# orbiphone.net
KiCad netlist of a schematic drawn in EAGLE
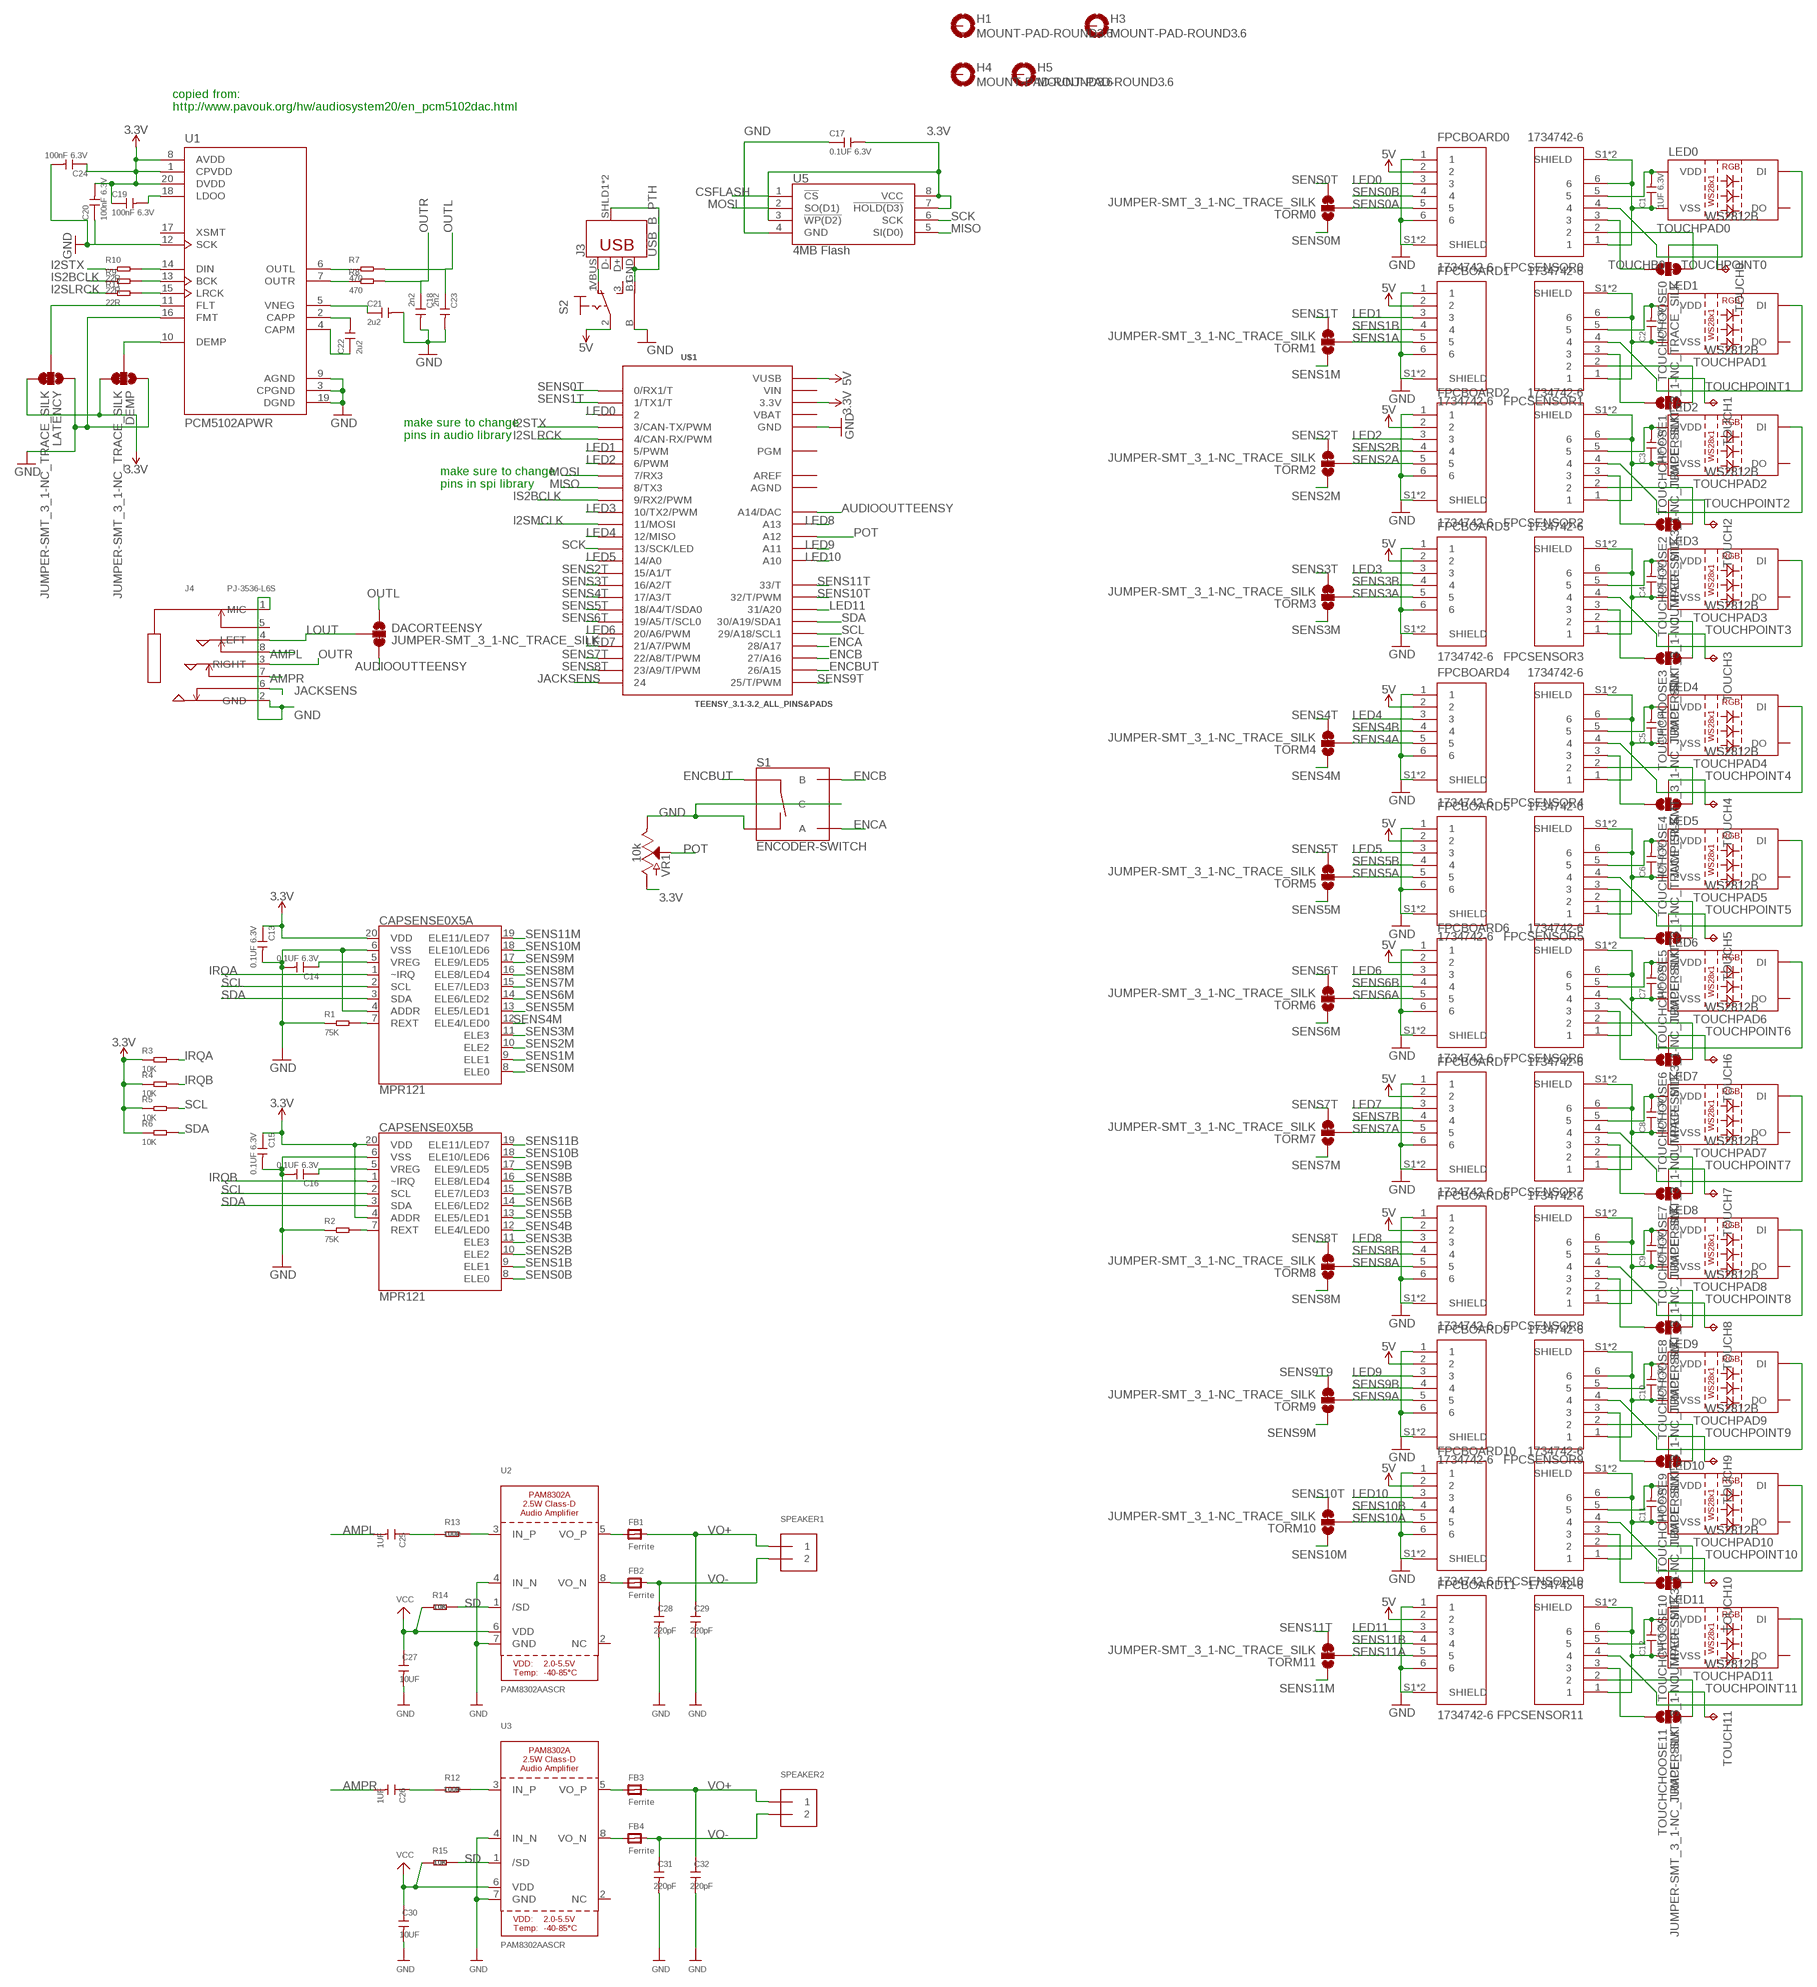
[diagram p0: schematic, sheet 1]

(export (version "E")
  (design (tool "Eeschema 10.0.6"))
  (components
    (comp (ref "C1")
      (value "1UF 6.3V")
      (footprint "eagle-import:C0402")
      (fields (field (name "MPN") "CC0402KRX5R5BB105"))
      (libsource (lib "eagle-import") (part "CERAMIC-1UF-6.3V-10%-X5R(0402)"))
    )
    (comp (ref "C2")
      (value "1UF 6.3V")
      (footprint "eagle-import:C0402")
      (fields (field (name "MPN") "CC0402KRX5R5BB105"))
      (libsource (lib "eagle-import") (part "CERAMIC-1UF-6.3V-10%-X5R(0402)"))
    )
    (comp (ref "C3")
      (value "1UF 6.3V")
      (footprint "eagle-import:C0402")
      (fields (field (name "MPN") "CC0402KRX5R5BB105"))
      (libsource (lib "eagle-import") (part "CERAMIC-1UF-6.3V-10%-X5R(0402)"))
    )
    (comp (ref "C4")
      (value "1UF 6.3V")
      (footprint "eagle-import:C0402")
      (fields (field (name "MPN") "CC0402KRX5R5BB105"))
      (libsource (lib "eagle-import") (part "CERAMIC-1UF-6.3V-10%-X5R(0402)"))
    )
    (comp (ref "C5")
      (value "1UF 6.3V")
      (footprint "eagle-import:C0402")
      (fields (field (name "MPN") "CC0402KRX5R5BB105"))
      (libsource (lib "eagle-import") (part "CERAMIC-1UF-6.3V-10%-X5R(0402)"))
    )
    (comp (ref "C6")
      (value "1UF 6.3V")
      (footprint "eagle-import:C0402")
      (fields (field (name "MPN") "CC0402KRX5R5BB105"))
      (libsource (lib "eagle-import") (part "CERAMIC-1UF-6.3V-10%-X5R(0402)"))
    )
    (comp (ref "C7")
      (value "1UF 6.3V")
      (footprint "eagle-import:C0402")
      (fields (field (name "MPN") "CC0402KRX5R5BB105"))
      (libsource (lib "eagle-import") (part "CERAMIC-1UF-6.3V-10%-X5R(0402)"))
    )
    (comp (ref "C8")
      (value "1UF 6.3V")
      (footprint "eagle-import:C0402")
      (fields (field (name "MPN") "CC0402KRX5R5BB105"))
      (libsource (lib "eagle-import") (part "CERAMIC-1UF-6.3V-10%-X5R(0402)"))
    )
    (comp (ref "C9")
      (value "1UF 6.3V")
      (footprint "eagle-import:C0402")
      (fields (field (name "MPN") "CC0402KRX5R5BB105"))
      (libsource (lib "eagle-import") (part "CERAMIC-1UF-6.3V-10%-X5R(0402)"))
    )
    (comp (ref "C10")
      (value "1UF 6.3V")
      (footprint "eagle-import:C0402")
      (fields (field (name "MPN") "CC0402KRX5R5BB105"))
      (libsource (lib "eagle-import") (part "CERAMIC-1UF-6.3V-10%-X5R(0402)"))
    )
    (comp (ref "C11")
      (value "1UF 6.3V")
      (footprint "eagle-import:C0402")
      (fields (field (name "MPN") "CC0402KRX5R5BB105"))
      (libsource (lib "eagle-import") (part "CERAMIC-1UF-6.3V-10%-X5R(0402)"))
    )
    (comp (ref "C12")
      (value "1UF 6.3V")
      (footprint "eagle-import:C0402")
      (fields (field (name "MPN") "CC0402KRX5R5BB105"))
      (libsource (lib "eagle-import") (part "CERAMIC-1UF-6.3V-10%-X5R(0402)"))
    )
    (comp (ref "C13")
      (value "0.1UF 6.3V")
      (footprint "eagle-import:C0402")
      (fields (field (name "MPN") "CC0402KRX5R5BB105"))
      (libsource (lib "eagle-import") (part "CERAMIC-1UF-6.3V-10%-X5R(0402)"))
    )
    (comp (ref "C14")
      (value "0.1UF 6.3V")
      (footprint "eagle-import:C0402")
      (fields (field (name "MPN") "CC0402KRX5R5BB105"))
      (libsource (lib "eagle-import") (part "CERAMIC-1UF-6.3V-10%-X5R(0402)"))
    )
    (comp (ref "C15")
      (value "0.1UF 6.3V")
      (footprint "eagle-import:C0402")
      (fields (field (name "MPN") "CC0402KRX5R5BB105"))
      (libsource (lib "eagle-import") (part "CERAMIC-1UF-6.3V-10%-X5R(0402)"))
    )
    (comp (ref "C16")
      (value "0.1UF 6.3V")
      (footprint "eagle-import:C0402")
      (fields (field (name "MPN") "CC0402KRX5R5BB105"))
      (libsource (lib "eagle-import") (part "CERAMIC-1UF-6.3V-10%-X5R(0402)"))
    )
    (comp (ref "C17")
      (value "0.1UF 6.3V")
      (footprint "eagle-import:C0402")
      (fields (field (name "MPN") "CC0402KRX5R5BB105"))
      (libsource (lib "eagle-import") (part "CERAMIC-1UF-6.3V-10%-X5R(0402)"))
    )
    (comp (ref "C18")
      (value "2n2")
      (footprint "eagle-import:C0402")
      (fields (field (name "MPN") "CC0402KRX5R5BB105"))
      (libsource (lib "eagle-import") (part "CERAMIC-1UF-6.3V-10%-X5R(0402)"))
    )
    (comp (ref "C19")
      (value "100nF 6.3V")
      (footprint "eagle-import:C0402")
      (fields (field (name "MPN") "CC0402KRX5R5BB105"))
      (libsource (lib "eagle-import") (part "CERAMIC-1UF-6.3V-10%-X5R(0402)"))
    )
    (comp (ref "C20")
      (value "100nF 6.3V")
      (footprint "eagle-import:C0402")
      (fields (field (name "MPN") "CC0402KRX5R5BB105"))
      (libsource (lib "eagle-import") (part "CERAMIC-1UF-6.3V-10%-X5R(0402)"))
    )
    (comp (ref "C21")
      (value "2u2")
      (footprint "eagle-import:C0402")
      (fields (field (name "MPN") "CC0402KRX5R5BB105"))
      (libsource (lib "eagle-import") (part "CERAMIC-1UF-6.3V-10%-X5R(0402)"))
    )
    (comp (ref "C22")
      (value "2u2")
      (footprint "eagle-import:C0402")
      (fields (field (name "MPN") "CC0402KRX5R5BB105"))
      (libsource (lib "eagle-import") (part "CERAMIC-1UF-6.3V-10%-X5R(0402)"))
    )
    (comp (ref "C23")
      (value "2n2")
      (footprint "eagle-import:C0402")
      (fields (field (name "MPN") "CC0402KRX5R5BB105"))
      (libsource (lib "eagle-import") (part "CERAMIC-1UF-6.3V-10%-X5R(0402)"))
    )
    (comp (ref "C24")
      (value "100nF 6.3V")
      (footprint "eagle-import:C0402")
      (fields (field (name "MPN") "CC0402KRX5R5BB105"))
      (libsource (lib "eagle-import") (part "CERAMIC-1UF-6.3V-10%-X5R(0402)"))
    )
    (comp (ref "C25")
      (value "1UF")
      (footprint "eagle-import:C0402")
      (fields (field (name "MPN") "CC0402KRX5R5BB105"))
      (libsource (lib "eagle-import") (part "CERAMIC-1UF-6.3V-10%-X5R(0402)"))
    )
    (comp (ref "C26")
      (value "1UF")
      (footprint "eagle-import:C0402")
      (fields (field (name "MPN") "CC0402KRX5R5BB105"))
      (libsource (lib "eagle-import") (part "CERAMIC-1UF-6.3V-10%-X5R(0402)"))
    )
    (comp (ref "C27")
      (value "10UF")
      (footprint "eagle-import:C0402")
      (fields (field (name "MPN") "CC0402KRX5R5BB105"))
      (libsource (lib "eagle-import") (part "CERAMIC-1UF-6.3V-10%-X5R(0402)"))
    )
    (comp (ref "C28")
      (value "220pF")
      (footprint "eagle-import:C0402")
      (fields (field (name "MPN") "CC0402KRX5R5BB105"))
      (libsource (lib "eagle-import") (part "CERAMIC-1UF-6.3V-10%-X5R(0402)"))
    )
    (comp (ref "C29")
      (value "220pF")
      (footprint "eagle-import:C0402")
      (fields (field (name "MPN") "CC0402KRX5R5BB105"))
      (libsource (lib "eagle-import") (part "CERAMIC-1UF-6.3V-10%-X5R(0402)"))
    )
    (comp (ref "C30")
      (value "10UF")
      (footprint "eagle-import:C0402")
      (fields (field (name "MPN") "CC0402KRX5R5BB105"))
      (libsource (lib "eagle-import") (part "CERAMIC-1UF-6.3V-10%-X5R(0402)"))
    )
    (comp (ref "C31")
      (value "220pF")
      (footprint "eagle-import:C0402")
      (fields (field (name "MPN") "CC0402KRX5R5BB105"))
      (libsource (lib "eagle-import") (part "CERAMIC-1UF-6.3V-10%-X5R(0402)"))
    )
    (comp (ref "C32")
      (value "220pF")
      (footprint "eagle-import:C0402")
      (fields (field (name "MPN") "CC0402KRX5R5BB105"))
      (libsource (lib "eagle-import") (part "CERAMIC-1UF-6.3V-10%-X5R(0402)"))
    )
    (comp (ref "CAPSENSE0X5A")
      (value "MPR121")
      (footprint "eagle-import:QFN-20")
      (libsource (lib "eagle-import") (part "MPR121"))
    )
    (comp (ref "CAPSENSE0X5B")
      (value "MPR121")
      (footprint "eagle-import:QFN-20")
      (libsource (lib "eagle-import") (part "MPR121"))
    )
    (comp (ref "DACORTEENSY")
      (value "JUMPER-SMT_3_1-NC_TRACE_SILK")
      (footprint "eagle-import:SMT-JUMPER_3_1-NC_TRACE_SILK")
      (libsource (lib "eagle-import") (part "JUMPER-SMT_3_1-NC_TRACE_SILK"))
    )
    (comp (ref "DEMP")
      (value "JUMPER-SMT_3_1-NC_TRACE_SILK")
      (footprint "eagle-import:SMT-JUMPER_3_1-NC_TRACE_SILK")
      (libsource (lib "eagle-import") (part "JUMPER-SMT_3_1-NC_TRACE_SILK"))
    )
    (comp (ref "FB1")
      (value "Ferrite")
      (footprint "eagle-import:_0805")
      (libsource (lib "eagle-import") (part "FERRITE_0805"))
    )
    (comp (ref "FB2")
      (value "Ferrite")
      (footprint "eagle-import:_0805")
      (libsource (lib "eagle-import") (part "FERRITE_0805"))
    )
    (comp (ref "FB3")
      (value "Ferrite")
      (footprint "eagle-import:_0805")
      (libsource (lib "eagle-import") (part "FERRITE_0805"))
    )
    (comp (ref "FB4")
      (value "Ferrite")
      (footprint "eagle-import:_0805")
      (libsource (lib "eagle-import") (part "FERRITE_0805"))
    )
    (comp (ref "FPCBOARD0")
      (value "1734742-6")
      (footprint "eagle-import:TE_1734742-6")
      (fields (field (name "MF") "TE Connectivity"))
      (libsource (lib "eagle-import") (part "1734742-6"))
    )
    (comp (ref "FPCBOARD1")
      (value "1734742-6")
      (footprint "eagle-import:TE_1734742-6")
      (fields (field (name "MF") "TE Connectivity"))
      (libsource (lib "eagle-import") (part "1734742-6"))
    )
    (comp (ref "FPCBOARD2")
      (value "1734742-6")
      (footprint "eagle-import:TE_1734742-6")
      (fields (field (name "MF") "TE Connectivity"))
      (libsource (lib "eagle-import") (part "1734742-6"))
    )
    (comp (ref "FPCBOARD3")
      (value "1734742-6")
      (footprint "eagle-import:TE_1734742-6")
      (fields (field (name "MF") "TE Connectivity"))
      (libsource (lib "eagle-import") (part "1734742-6"))
    )
    (comp (ref "FPCBOARD4")
      (value "1734742-6")
      (footprint "eagle-import:TE_1734742-6")
      (fields (field (name "MF") "TE Connectivity"))
      (libsource (lib "eagle-import") (part "1734742-6"))
    )
    (comp (ref "FPCBOARD5")
      (value "1734742-6")
      (footprint "eagle-import:TE_1734742-6")
      (fields (field (name "MF") "TE Connectivity"))
      (libsource (lib "eagle-import") (part "1734742-6"))
    )
    (comp (ref "FPCBOARD6")
      (value "1734742-6")
      (footprint "eagle-import:TE_1734742-6")
      (fields (field (name "MF") "TE Connectivity"))
      (libsource (lib "eagle-import") (part "1734742-6"))
    )
    (comp (ref "FPCBOARD7")
      (value "1734742-6")
      (footprint "eagle-import:TE_1734742-6")
      (fields (field (name "MF") "TE Connectivity"))
      (libsource (lib "eagle-import") (part "1734742-6"))
    )
    (comp (ref "FPCBOARD8")
      (value "1734742-6")
      (footprint "eagle-import:TE_1734742-6")
      (fields (field (name "MF") "TE Connectivity"))
      (libsource (lib "eagle-import") (part "1734742-6"))
    )
    (comp (ref "FPCBOARD9")
      (value "1734742-6")
      (footprint "eagle-import:TE_1734742-6")
      (fields (field (name "MF") "TE Connectivity"))
      (libsource (lib "eagle-import") (part "1734742-6"))
    )
    (comp (ref "FPCBOARD10")
      (value "1734742-6")
      (footprint "eagle-import:TE_1734742-6")
      (fields (field (name "MF") "TE Connectivity"))
      (libsource (lib "eagle-import") (part "1734742-6"))
    )
    (comp (ref "FPCBOARD11")
      (value "1734742-6")
      (footprint "eagle-import:TE_1734742-6")
      (fields (field (name "MF") "TE Connectivity"))
      (libsource (lib "eagle-import") (part "1734742-6"))
    )
    (comp (ref "FPCSENSOR0")
      (value "1734742-6")
      (footprint "eagle-import:TE_1734742-6")
      (fields (field (name "MF") "TE Connectivity"))
      (libsource (lib "eagle-import") (part "1734742-6"))
    )
    (comp (ref "FPCSENSOR1")
      (value "1734742-6")
      (footprint "eagle-import:TE_1734742-6")
      (fields (field (name "MF") "TE Connectivity"))
      (libsource (lib "eagle-import") (part "1734742-6"))
    )
    (comp (ref "FPCSENSOR2")
      (value "1734742-6")
      (footprint "eagle-import:TE_1734742-6")
      (fields (field (name "MF") "TE Connectivity"))
      (libsource (lib "eagle-import") (part "1734742-6"))
    )
    (comp (ref "FPCSENSOR3")
      (value "1734742-6")
      (footprint "eagle-import:TE_1734742-6")
      (fields (field (name "MF") "TE Connectivity"))
      (libsource (lib "eagle-import") (part "1734742-6"))
    )
    (comp (ref "FPCSENSOR4")
      (value "1734742-6")
      (footprint "eagle-import:TE_1734742-6")
      (fields (field (name "MF") "TE Connectivity"))
      (libsource (lib "eagle-import") (part "1734742-6"))
    )
    (comp (ref "FPCSENSOR5")
      (value "1734742-6")
      (footprint "eagle-import:TE_1734742-6")
      (fields (field (name "MF") "TE Connectivity"))
      (libsource (lib "eagle-import") (part "1734742-6"))
    )
    (comp (ref "FPCSENSOR6")
      (value "1734742-6")
      (footprint "eagle-import:TE_1734742-6")
      (fields (field (name "MF") "TE Connectivity"))
      (libsource (lib "eagle-import") (part "1734742-6"))
    )
    (comp (ref "FPCSENSOR7")
      (value "1734742-6")
      (footprint "eagle-import:TE_1734742-6")
      (fields (field (name "MF") "TE Connectivity"))
      (libsource (lib "eagle-import") (part "1734742-6"))
    )
    (comp (ref "FPCSENSOR8")
      (value "1734742-6")
      (footprint "eagle-import:TE_1734742-6")
      (fields (field (name "MF") "TE Connectivity"))
      (libsource (lib "eagle-import") (part "1734742-6"))
    )
    (comp (ref "FPCSENSOR9")
      (value "1734742-6")
      (footprint "eagle-import:TE_1734742-6")
      (fields (field (name "MF") "TE Connectivity"))
      (libsource (lib "eagle-import") (part "1734742-6"))
    )
    (comp (ref "FPCSENSOR10")
      (value "1734742-6")
      (footprint "eagle-import:TE_1734742-6")
      (fields (field (name "MF") "TE Connectivity"))
      (libsource (lib "eagle-import") (part "1734742-6"))
    )
    (comp (ref "FPCSENSOR11")
      (value "1734742-6")
      (footprint "eagle-import:TE_1734742-6")
      (fields (field (name "MF") "TE Connectivity"))
      (libsource (lib "eagle-import") (part "1734742-6"))
    )
    (comp (ref "H1")
      (value "MOUNT-PAD-ROUND3.6")
      (footprint "eagle-import:3,6-PAD")
      (libsource (lib "eagle-import") (part "MOUNT-PAD-ROUND3.6"))
    )
    (comp (ref "H3")
      (value "MOUNT-PAD-ROUND3.6")
      (footprint "eagle-import:3,6-PAD")
      (libsource (lib "eagle-import") (part "MOUNT-PAD-ROUND3.6"))
    )
    (comp (ref "H4")
      (value "MOUNT-PAD-ROUND3.6")
      (footprint "eagle-import:3,6-PAD")
      (libsource (lib "eagle-import") (part "MOUNT-PAD-ROUND3.6"))
    )
    (comp (ref "H5")
      (value "MOUNT-PAD-ROUND3.6")
      (footprint "eagle-import:3,6-PAD")
      (libsource (lib "eagle-import") (part "MOUNT-PAD-ROUND3.6"))
    )
    (comp (ref "J3")
      (value "USB_B_PTH")
      (footprint "eagle-import:USB-B-PTH")
      (libsource (lib "eagle-import") (part "USB_B_PTH"))
    )
    (comp (ref "J4")
      (value "PJ-3536-L6S")
      (footprint "eagle-import:AUDIO8P-SMD-3.5-14.5X6X5MM")
      (libsource (lib "eagle-import") (part "AUDIO-JACK-SMD-8P(PJ-3536-L6S)"))
    )
    (comp (ref "LATENCY")
      (value "JUMPER-SMT_3_1-NC_TRACE_SILK")
      (footprint "eagle-import:SMT-JUMPER_3_1-NC_TRACE_SILK")
      (libsource (lib "eagle-import") (part "JUMPER-SMT_3_1-NC_TRACE_SILK"))
    )
    (comp (ref "LED0")
      (value "WS2812B")
      (footprint "eagle-import:WS2812B")
      (libsource (lib "eagle-import") (part "WS2812B"))
    )
    (comp (ref "LED1")
      (value "WS2812B")
      (footprint "eagle-import:WS2812B")
      (libsource (lib "eagle-import") (part "WS2812B"))
    )
    (comp (ref "LED2")
      (value "WS2812B")
      (footprint "eagle-import:WS2812B")
      (libsource (lib "eagle-import") (part "WS2812B"))
    )
    (comp (ref "LED3")
      (value "WS2812B")
      (footprint "eagle-import:WS2812B")
      (libsource (lib "eagle-import") (part "WS2812B"))
    )
    (comp (ref "LED4")
      (value "WS2812B")
      (footprint "eagle-import:WS2812B")
      (libsource (lib "eagle-import") (part "WS2812B"))
    )
    (comp (ref "LED5")
      (value "WS2812B")
      (footprint "eagle-import:WS2812B")
      (libsource (lib "eagle-import") (part "WS2812B"))
    )
    (comp (ref "LED6")
      (value "WS2812B")
      (footprint "eagle-import:WS2812B")
      (libsource (lib "eagle-import") (part "WS2812B"))
    )
    (comp (ref "LED7")
      (value "WS2812B")
      (footprint "eagle-import:WS2812B")
      (libsource (lib "eagle-import") (part "WS2812B"))
    )
    (comp (ref "LED8")
      (value "WS2812B")
      (footprint "eagle-import:WS2812B")
      (libsource (lib "eagle-import") (part "WS2812B"))
    )
    (comp (ref "LED9")
      (value "WS2812B")
      (footprint "eagle-import:WS2812B")
      (libsource (lib "eagle-import") (part "WS2812B"))
    )
    (comp (ref "LED10")
      (value "WS2812B")
      (footprint "eagle-import:WS2812B")
      (libsource (lib "eagle-import") (part "WS2812B"))
    )
    (comp (ref "LED11")
      (value "WS2812B")
      (footprint "eagle-import:WS2812B")
      (libsource (lib "eagle-import") (part "WS2812B"))
    )
    (comp (ref "R1")
      (value "75K")
      (footprint "eagle-import:R0603")
      (fields (field (name "MPN") "RC0603FR-071K5L"))
      (libsource (lib "eagle-import") (part "SMD-RES-75K-1%-1/10W(0603)"))
    )
    (comp (ref "R2")
      (value "75K")
      (footprint "eagle-import:R0603")
      (fields (field (name "MPN") "RC0603FR-071K5L"))
      (libsource (lib "eagle-import") (part "SMD-RES-75K-1%-1/10W(0603)"))
    )
    (comp (ref "R3")
      (value "10K")
      (footprint "eagle-import:R0603")
      (fields (field (name "MPN") "RC0603FR-071K5L"))
      (libsource (lib "eagle-import") (part "SMD-RES-75K-1%-1/10W(0603)"))
    )
    (comp (ref "R4")
      (value "10K")
      (footprint "eagle-import:R0603")
      (fields (field (name "MPN") "RC0603FR-071K5L"))
      (libsource (lib "eagle-import") (part "SMD-RES-75K-1%-1/10W(0603)"))
    )
    (comp (ref "R5")
      (value "10K")
      (footprint "eagle-import:R0603")
      (fields (field (name "MPN") "RC0603FR-071K5L"))
      (libsource (lib "eagle-import") (part "SMD-RES-75K-1%-1/10W(0603)"))
    )
    (comp (ref "R6")
      (value "10K")
      (footprint "eagle-import:R0603")
      (fields (field (name "MPN") "RC0603FR-071K5L"))
      (libsource (lib "eagle-import") (part "SMD-RES-75K-1%-1/10W(0603)"))
    )
    (comp (ref "R7")
      (value "470")
      (footprint "eagle-import:R0603")
      (fields (field (name "MPN") "RC0603FR-071K5L"))
      (libsource (lib "eagle-import") (part "SMD-RES-75K-1%-1/10W(0603)"))
    )
    (comp (ref "R8")
      (value "470")
      (footprint "eagle-import:R0603")
      (fields (field (name "MPN") "RC0603FR-071K5L"))
      (libsource (lib "eagle-import") (part "SMD-RES-75K-1%-1/10W(0603)"))
    )
    (comp (ref "R9")
      (value "22R")
      (footprint "eagle-import:R0603")
      (fields (field (name "MPN") "RC0603FR-071K5L"))
      (libsource (lib "eagle-import") (part "SMD-RES-75K-1%-1/10W(0603)"))
    )
    (comp (ref "R10")
      (value "22R")
      (footprint "eagle-import:R0603")
      (fields (field (name "MPN") "RC0603FR-071K5L"))
      (libsource (lib "eagle-import") (part "SMD-RES-75K-1%-1/10W(0603)"))
    )
    (comp (ref "R11")
      (value "22R")
      (footprint "eagle-import:R0603")
      (fields (field (name "MPN") "RC0603FR-071K5L"))
      (libsource (lib "eagle-import") (part "SMD-RES-75K-1%-1/10W(0603)"))
    )
    (comp (ref "R12")
      (value "100R")
      (footprint "eagle-import:R0805")
      (fields (field (name "MPN") "RC0805JR-071KL"))
      (libsource (lib "eagle-import") (part "SMD-RES-100R-1%-1/8W(0805)"))
    )
    (comp (ref "R13")
      (value "100R")
      (footprint "eagle-import:R0805")
      (fields (field (name "MPN") "RC0805JR-071KL"))
      (libsource (lib "eagle-import") (part "SMD-RES-100R-1%-1/8W(0805)"))
    )
    (comp (ref "R14")
      (value "10K")
      (footprint "eagle-import:R0805")
      (fields (field (name "MPN") "RC0805JR-071KL"))
      (libsource (lib "eagle-import") (part "SMD-RES-100R-1%-1/8W(0805)"))
    )
    (comp (ref "R15")
      (value "10K")
      (footprint "eagle-import:R0805")
      (fields (field (name "MPN") "RC0805JR-071KL"))
      (libsource (lib "eagle-import") (part "SMD-RES-100R-1%-1/8W(0805)"))
    )
    (comp (ref "S1")
      (value "ENCODER-SWITCH")
      (footprint "eagle-import:ROTARY_ENC_PLAIN")
      (libsource (lib "eagle-import") (part "ENCODER-SWITCH"))
    )
    (comp (ref "S2")
      (value "316-917")
      (footprint "eagle-import:316-917")
      (libsource (lib "eagle-import") (part "316-917"))
    )
    (comp (ref "SPEAKER1")
      (value "TERMBLOCK_1X2")
      (footprint "eagle-import:TERMBLOCK_1X2-3.5MM")
      (libsource (lib "eagle-import") (part "TERMBLOCK_1X2"))
    )
    (comp (ref "SPEAKER2")
      (value "TERMBLOCK_1X2")
      (footprint "eagle-import:TERMBLOCK_1X2-3.5MM")
      (libsource (lib "eagle-import") (part "TERMBLOCK_1X2"))
    )
    (comp (ref "TORM0")
      (value "JUMPER-SMT_3_1-NC_TRACE_SILK")
      (footprint "eagle-import:SMT-JUMPER_3_1-NC_TRACE_SILK")
      (libsource (lib "eagle-import") (part "JUMPER-SMT_3_1-NC_TRACE_SILK"))
    )
    (comp (ref "TORM1")
      (value "JUMPER-SMT_3_1-NC_TRACE_SILK")
      (footprint "eagle-import:SMT-JUMPER_3_1-NC_TRACE_SILK")
      (libsource (lib "eagle-import") (part "JUMPER-SMT_3_1-NC_TRACE_SILK"))
    )
    (comp (ref "TORM2")
      (value "JUMPER-SMT_3_1-NC_TRACE_SILK")
      (footprint "eagle-import:SMT-JUMPER_3_1-NC_TRACE_SILK")
      (libsource (lib "eagle-import") (part "JUMPER-SMT_3_1-NC_TRACE_SILK"))
    )
    (comp (ref "TORM3")
      (value "JUMPER-SMT_3_1-NC_TRACE_SILK")
      (footprint "eagle-import:SMT-JUMPER_3_1-NC_TRACE_SILK")
      (libsource (lib "eagle-import") (part "JUMPER-SMT_3_1-NC_TRACE_SILK"))
    )
    (comp (ref "TORM4")
      (value "JUMPER-SMT_3_1-NC_TRACE_SILK")
      (footprint "eagle-import:SMT-JUMPER_3_1-NC_TRACE_SILK")
      (libsource (lib "eagle-import") (part "JUMPER-SMT_3_1-NC_TRACE_SILK"))
    )
    (comp (ref "TORM5")
      (value "JUMPER-SMT_3_1-NC_TRACE_SILK")
      (footprint "eagle-import:SMT-JUMPER_3_1-NC_TRACE_SILK")
      (libsource (lib "eagle-import") (part "JUMPER-SMT_3_1-NC_TRACE_SILK"))
    )
    (comp (ref "TORM6")
      (value "JUMPER-SMT_3_1-NC_TRACE_SILK")
      (footprint "eagle-import:SMT-JUMPER_3_1-NC_TRACE_SILK")
      (libsource (lib "eagle-import") (part "JUMPER-SMT_3_1-NC_TRACE_SILK"))
    )
    (comp (ref "TORM7")
      (value "JUMPER-SMT_3_1-NC_TRACE_SILK")
      (footprint "eagle-import:SMT-JUMPER_3_1-NC_TRACE_SILK")
      (libsource (lib "eagle-import") (part "JUMPER-SMT_3_1-NC_TRACE_SILK"))
    )
    (comp (ref "TORM8")
      (value "JUMPER-SMT_3_1-NC_TRACE_SILK")
      (footprint "eagle-import:SMT-JUMPER_3_1-NC_TRACE_SILK")
      (libsource (lib "eagle-import") (part "JUMPER-SMT_3_1-NC_TRACE_SILK"))
    )
    (comp (ref "TORM9")
      (value "JUMPER-SMT_3_1-NC_TRACE_SILK")
      (footprint "eagle-import:SMT-JUMPER_3_1-NC_TRACE_SILK")
      (libsource (lib "eagle-import") (part "JUMPER-SMT_3_1-NC_TRACE_SILK"))
    )
    (comp (ref "TORM10")
      (value "JUMPER-SMT_3_1-NC_TRACE_SILK")
      (footprint "eagle-import:SMT-JUMPER_3_1-NC_TRACE_SILK")
      (libsource (lib "eagle-import") (part "JUMPER-SMT_3_1-NC_TRACE_SILK"))
    )
    (comp (ref "TORM11")
      (value "JUMPER-SMT_3_1-NC_TRACE_SILK")
      (footprint "eagle-import:SMT-JUMPER_3_1-NC_TRACE_SILK")
      (libsource (lib "eagle-import") (part "JUMPER-SMT_3_1-NC_TRACE_SILK"))
    )
    (comp (ref "TOUCH0")
      (value "TPPAD1-13")
      (footprint "eagle-import:P1-13")
      (libsource (lib "eagle-import") (part "TPPAD1-13"))
    )
    (comp (ref "TOUCH1")
      (value "TPPAD1-13")
      (footprint "eagle-import:P1-13")
      (libsource (lib "eagle-import") (part "TPPAD1-13"))
    )
    (comp (ref "TOUCH2")
      (value "TPPAD1-13")
      (footprint "eagle-import:P1-13")
      (libsource (lib "eagle-import") (part "TPPAD1-13"))
    )
    (comp (ref "TOUCH3")
      (value "TPPAD1-13")
      (footprint "eagle-import:P1-13")
      (libsource (lib "eagle-import") (part "TPPAD1-13"))
    )
    (comp (ref "TOUCH4")
      (value "TPPAD1-13")
      (footprint "eagle-import:P1-13")
      (libsource (lib "eagle-import") (part "TPPAD1-13"))
    )
    (comp (ref "TOUCH5")
      (value "TPPAD1-13")
      (footprint "eagle-import:P1-13")
      (libsource (lib "eagle-import") (part "TPPAD1-13"))
    )
    (comp (ref "TOUCH6")
      (value "TPPAD1-13")
      (footprint "eagle-import:P1-13")
      (libsource (lib "eagle-import") (part "TPPAD1-13"))
    )
    (comp (ref "TOUCH7")
      (value "TPPAD1-13")
      (footprint "eagle-import:P1-13")
      (libsource (lib "eagle-import") (part "TPPAD1-13"))
    )
    (comp (ref "TOUCH8")
      (value "TPPAD1-13")
      (footprint "eagle-import:P1-13")
      (libsource (lib "eagle-import") (part "TPPAD1-13"))
    )
    (comp (ref "TOUCH9")
      (value "TPPAD1-13")
      (footprint "eagle-import:P1-13")
      (libsource (lib "eagle-import") (part "TPPAD1-13"))
    )
    (comp (ref "TOUCH10")
      (value "TPPAD1-13")
      (footprint "eagle-import:P1-13")
      (libsource (lib "eagle-import") (part "TPPAD1-13"))
    )
    (comp (ref "TOUCH11")
      (value "TPPAD1-13")
      (footprint "eagle-import:P1-13")
      (libsource (lib "eagle-import") (part "TPPAD1-13"))
    )
    (comp (ref "TOUCHCHOOSE0")
      (value "JUMPER-SMT_3_1-NC_TRACE_SILK")
      (footprint "eagle-import:SMT-JUMPER_3_1-NC_TRACE_SILK")
      (libsource (lib "eagle-import") (part "JUMPER-SMT_3_1-NC_TRACE_SILK"))
    )
    (comp (ref "TOUCHCHOOSE1")
      (value "JUMPER-SMT_3_1-NC_TRACE_SILK")
      (footprint "eagle-import:SMT-JUMPER_3_1-NC_TRACE_SILK")
      (libsource (lib "eagle-import") (part "JUMPER-SMT_3_1-NC_TRACE_SILK"))
    )
    (comp (ref "TOUCHCHOOSE2")
      (value "JUMPER-SMT_3_1-NC_TRACE_SILK")
      (footprint "eagle-import:SMT-JUMPER_3_1-NC_TRACE_SILK")
      (libsource (lib "eagle-import") (part "JUMPER-SMT_3_1-NC_TRACE_SILK"))
    )
    (comp (ref "TOUCHCHOOSE3")
      (value "JUMPER-SMT_3_1-NC_TRACE_SILK")
      (footprint "eagle-import:SMT-JUMPER_3_1-NC_TRACE_SILK")
      (libsource (lib "eagle-import") (part "JUMPER-SMT_3_1-NC_TRACE_SILK"))
    )
    (comp (ref "TOUCHCHOOSE4")
      (value "JUMPER-SMT_3_1-NC_TRACE_SILK")
      (footprint "eagle-import:SMT-JUMPER_3_1-NC_TRACE_SILK")
      (libsource (lib "eagle-import") (part "JUMPER-SMT_3_1-NC_TRACE_SILK"))
    )
    (comp (ref "TOUCHCHOOSE5")
      (value "JUMPER-SMT_3_1-NC_TRACE_SILK")
      (footprint "eagle-import:SMT-JUMPER_3_1-NC_TRACE_SILK")
      (libsource (lib "eagle-import") (part "JUMPER-SMT_3_1-NC_TRACE_SILK"))
    )
    (comp (ref "TOUCHCHOOSE6")
      (value "JUMPER-SMT_3_1-NC_TRACE_SILK")
      (footprint "eagle-import:SMT-JUMPER_3_1-NC_TRACE_SILK")
      (libsource (lib "eagle-import") (part "JUMPER-SMT_3_1-NC_TRACE_SILK"))
    )
    (comp (ref "TOUCHCHOOSE7")
      (value "JUMPER-SMT_3_1-NC_TRACE_SILK")
      (footprint "eagle-import:SMT-JUMPER_3_1-NC_TRACE_SILK")
      (libsource (lib "eagle-import") (part "JUMPER-SMT_3_1-NC_TRACE_SILK"))
    )
    (comp (ref "TOUCHCHOOSE8")
      (value "JUMPER-SMT_3_1-NC_TRACE_SILK")
      (footprint "eagle-import:SMT-JUMPER_3_1-NC_TRACE_SILK")
      (libsource (lib "eagle-import") (part "JUMPER-SMT_3_1-NC_TRACE_SILK"))
    )
    (comp (ref "TOUCHCHOOSE9")
      (value "JUMPER-SMT_3_1-NC_TRACE_SILK")
      (footprint "eagle-import:SMT-JUMPER_3_1-NC_TRACE_SILK")
      (libsource (lib "eagle-import") (part "JUMPER-SMT_3_1-NC_TRACE_SILK"))
    )
    (comp (ref "TOUCHCHOOSE10")
      (value "JUMPER-SMT_3_1-NC_TRACE_SILK")
      (footprint "eagle-import:SMT-JUMPER_3_1-NC_TRACE_SILK")
      (libsource (lib "eagle-import") (part "JUMPER-SMT_3_1-NC_TRACE_SILK"))
    )
    (comp (ref "TOUCHCHOOSE11")
      (value "JUMPER-SMT_3_1-NC_TRACE_SILK")
      (footprint "eagle-import:SMT-JUMPER_3_1-NC_TRACE_SILK")
      (libsource (lib "eagle-import") (part "JUMPER-SMT_3_1-NC_TRACE_SILK"))
    )
    (comp (ref "U$1")
      (value "TEENSY_3.1-3.2_ALL_PINS&PADS")
      (footprint "eagle-import:TEENSY_3.0-3.2_ALL_PINS_&_PADS")
      (libsource (lib "eagle-import") (part "TEENSY_3.1-3.2_ALL_PINS&PADS"))
    )
    (comp (ref "U1")
      (value "PCM5102APWR")
      (footprint "eagle-import:SOP65P640X120-20N")
      (fields (field (name "MF") "Texas Instruments"))
      (libsource (lib "eagle-import") (part "PCM5102APWR"))
    )
    (comp (ref "U2")
      (value "PAM8302AASCR")
      (footprint "eagle-import:MSOP8_0.65MM")
      (libsource (lib "eagle-import") (part "AUDIOAMP_PAM8302A"))
    )
    (comp (ref "U3")
      (value "PAM8302AASCR")
      (footprint "eagle-import:MSOP8_0.65MM")
      (libsource (lib "eagle-import") (part "AUDIOAMP_PAM8302A"))
    )
    (comp (ref "U5")
      (value "4MB Flash")
      (footprint "eagle-import:SO08")
      (libsource (lib "eagle-import") (part "AT25SF041"))
    )
    (comp (ref "VR1")
      (value "10k")
      (footprint "eagle-import:POT-PTH-ALPS-KIT")
      (libsource (lib "eagle-import") (part "POTENTIOMETER-PTH-9MM-1/20W-20%-KIT"))
    )
  )
  (nets
    (net (code "1") (name "/AGND") (class "Default")
      (node (ref "U$1") (pin "AGND") (pinfunction "AGND_AGND") (pintype "power_in"))
    )
    (net (code "2") (name "/AMPL") (class "Default")
      (node (ref "C25") (pin "2") (pinfunction "2_2") (pintype "passive"))
      (node (ref "J4") (pin "8") (pinfunction "8_8") (pintype "bidirectional"))
    )
    (net (code "3") (name "/AMPR") (class "Default")
      (node (ref "C26") (pin "2") (pinfunction "2_2") (pintype "passive"))
      (node (ref "J4") (pin "7") (pinfunction "7_7") (pintype "bidirectional"))
    )
    (net (code "4") (name "/AREF") (class "Default")
      (node (ref "U$1") (pin "AREF") (pinfunction "AREF_AREF") (pintype "power_in"))
    )
    (net (code "5") (name "/AUDIOOUTTEENSY") (class "Default")
      (node (ref "DACORTEENSY") (pin "3") (pinfunction "3_3") (pintype "passive"))
      (node (ref "U$1") (pin "RESET/DAC") (pinfunction "A14/DAC_RESET/DAC") (pintype "bidirectional"))
    )
    (net (code "6") (name "/CSFLASH") (class "Default")
      (node (ref "U5") (pin "1") (pinfunction "~{CS}_1") (pintype "bidirectional"))
    )
    (net (code "7") (name "/ENCA") (class "Default")
      (node (ref "S1") (pin "A") (pinfunction "A_A") (pintype "bidirectional"))
      (node (ref "U$1") (pin "28") (pinfunction "28/A17_28") (pintype "bidirectional"))
    )
    (net (code "8") (name "/ENCB") (class "Default")
      (node (ref "S1") (pin "B") (pinfunction "B_B") (pintype "bidirectional"))
      (node (ref "U$1") (pin "27") (pinfunction "27/A16_27") (pintype "bidirectional"))
    )
    (net (code "9") (name "/ENCBUT") (class "Default")
      (node (ref "S1") (pin "SW+") (pinfunction "SW+_SW+") (pintype "bidirectional"))
      (node (ref "U$1") (pin "26") (pinfunction "26/A15_26") (pintype "bidirectional"))
    )
    (net (code "10") (name "/I2SLRCK") (class "Default")
      (node (ref "R11") (pin "1") (pinfunction "1_1") (pintype "passive"))
      (node (ref "U$1") (pin "4") (pinfunction "4/CAN-RX/PWM_4") (pintype "bidirectional"))
    )
    (net (code "11") (name "/I2SMCLK") (class "Default")
      (node (ref "U$1") (pin "11") (pinfunction "11/MOSI_11") (pintype "bidirectional"))
    )
    (net (code "12") (name "/I2STX") (class "Default")
      (node (ref "R10") (pin "1") (pinfunction "1_1") (pintype "passive"))
      (node (ref "U$1") (pin "3") (pinfunction "3/CAN-TX/PWM_3") (pintype "bidirectional"))
    )
    (net (code "13") (name "/IRQA") (class "Default")
      (node (ref "CAPSENSE0X5A") (pin "1") (pinfunction "~{IRQ}_1") (pintype "bidirectional"))
      (node (ref "R3") (pin "2") (pinfunction "2_2") (pintype "passive"))
    )
    (net (code "14") (name "/IRQB") (class "Default")
      (node (ref "CAPSENSE0X5B") (pin "1") (pinfunction "~{IRQ}_1") (pintype "bidirectional"))
      (node (ref "R4") (pin "2") (pinfunction "2_2") (pintype "passive"))
    )
    (net (code "15") (name "/IS2BCLK") (class "Default")
      (node (ref "R9") (pin "1") (pinfunction "1_1") (pintype "passive"))
      (node (ref "U$1") (pin "9") (pinfunction "9/RX2/PWM_9") (pintype "bidirectional"))
    )
    (net (code "16") (name "/JACKSENS") (class "Default")
      (node (ref "J4") (pin "6") (pinfunction "6_6") (pintype "bidirectional"))
      (node (ref "U$1") (pin "24") (pinfunction "24_24") (pintype "bidirectional"))
    )
    (net (code "17") (name "/LED0") (class "Default")
      (node (ref "FPCBOARD0") (pin "3") (pinfunction "3_3") (pintype "passive"))
      (node (ref "U$1") (pin "2") (pinfunction "2_2") (pintype "bidirectional"))
    )
    (net (code "18") (name "/LED1") (class "Default")
      (node (ref "FPCBOARD1") (pin "3") (pinfunction "3_3") (pintype "passive"))
      (node (ref "U$1") (pin "5") (pinfunction "5/PWM_5") (pintype "bidirectional"))
    )
    (net (code "19") (name "/LED2") (class "Default")
      (node (ref "FPCBOARD2") (pin "3") (pinfunction "3_3") (pintype "passive"))
      (node (ref "U$1") (pin "6") (pinfunction "6/PWM_6") (pintype "bidirectional"))
    )
    (net (code "20") (name "/LED3") (class "Default")
      (node (ref "FPCBOARD3") (pin "3") (pinfunction "3_3") (pintype "passive"))
      (node (ref "U$1") (pin "10") (pinfunction "10/TX2/PWM_10") (pintype "bidirectional"))
    )
    (net (code "21") (name "/LED4") (class "Default")
      (node (ref "FPCBOARD4") (pin "3") (pinfunction "3_3") (pintype "passive"))
      (node (ref "U$1") (pin "12") (pinfunction "12/MISO_12") (pintype "bidirectional"))
    )
    (net (code "22") (name "/LED5") (class "Default")
      (node (ref "FPCBOARD5") (pin "3") (pinfunction "3_3") (pintype "passive"))
      (node (ref "U$1") (pin "14/A0") (pinfunction "14/A0_14/A0") (pintype "bidirectional"))
    )
    (net (code "23") (name "/LED6") (class "Default")
      (node (ref "FPCBOARD6") (pin "3") (pinfunction "3_3") (pintype "passive"))
      (node (ref "U$1") (pin "20/A6") (pinfunction "20/A6/PWM_20/A6") (pintype "bidirectional"))
    )
    (net (code "24") (name "/LED7") (class "Default")
      (node (ref "FPCBOARD7") (pin "3") (pinfunction "3_3") (pintype "passive"))
      (node (ref "U$1") (pin "21/A7") (pinfunction "21/A7/PWM_21/A7") (pintype "bidirectional"))
    )
    (net (code "25") (name "/LED8") (class "Default")
      (node (ref "FPCBOARD8") (pin "3") (pinfunction "3_3") (pintype "passive"))
      (node (ref "U$1") (pin "A13") (pinfunction "A13_A13") (pintype "bidirectional"))
    )
    (net (code "26") (name "/LED9") (class "Default")
      (node (ref "FPCBOARD9") (pin "3") (pinfunction "3_3") (pintype "passive"))
      (node (ref "U$1") (pin "A11") (pinfunction "A11_A11") (pintype "bidirectional"))
    )
    (net (code "27") (name "/LED10") (class "Default")
      (node (ref "FPCBOARD10") (pin "3") (pinfunction "3_3") (pintype "passive"))
      (node (ref "U$1") (pin "A10") (pinfunction "A10_A10") (pintype "bidirectional"))
    )
    (net (code "28") (name "/LED11") (class "Default")
      (node (ref "FPCBOARD11") (pin "3") (pinfunction "3_3") (pintype "passive"))
      (node (ref "U$1") (pin "31") (pinfunction "31/A20_31") (pintype "bidirectional"))
    )
    (net (code "29") (name "/LOUT") (class "Default")
      (node (ref "DACORTEENSY") (pin "2") (pinfunction "2_2") (pintype "passive"))
      (node (ref "J4") (pin "4") (pinfunction "LEFT_4") (pintype "bidirectional"))
    )
    (net (code "30") (name "/MISO") (class "Default")
      (node (ref "U$1") (pin "8") (pinfunction "8/TX3_8") (pintype "bidirectional"))
      (node (ref "U5") (pin "5") (pinfunction "SI(D0)_5") (pintype "bidirectional"))
    )
    (net (code "31") (name "/MOSI") (class "Default")
      (node (ref "U$1") (pin "7") (pinfunction "7/RX3_7") (pintype "bidirectional"))
      (node (ref "U5") (pin "2") (pinfunction "SO(D1)_2") (pintype "bidirectional"))
    )
    (net (code "32") (name "/OUTL") (class "Default")
      (node (ref "C23") (pin "1") (pinfunction "1_1") (pintype "passive"))
      (node (ref "DACORTEENSY") (pin "1") (pinfunction "1_1") (pintype "passive"))
      (node (ref "R7") (pin "2") (pinfunction "2_2") (pintype "passive"))
    )
    (net (code "33") (name "/OUTR") (class "Default")
      (node (ref "C18") (pin "1") (pinfunction "1_1") (pintype "passive"))
      (node (ref "J4") (pin "3") (pinfunction "RIGHT_3") (pintype "bidirectional"))
      (node (ref "R8") (pin "2") (pinfunction "2_2") (pintype "passive"))
    )
    (net (code "34") (name "/POT") (class "Default")
      (node (ref "U$1") (pin "A12") (pinfunction "A12_A12") (pintype "bidirectional"))
      (node (ref "VR1") (pin "P$2") (pinfunction "S_P$2") (pintype "passive"))
    )
    (net (code "35") (name "/SCK") (class "Default")
      (node (ref "U$1") (pin "13") (pinfunction "13/SCK/LED_13") (pintype "bidirectional"))
      (node (ref "U5") (pin "6") (pinfunction "SCK_6") (pintype "bidirectional"))
    )
    (net (code "36") (name "/SCL") (class "Default")
      (node (ref "CAPSENSE0X5A") (pin "2") (pinfunction "SCL_2") (pintype "bidirectional"))
      (node (ref "CAPSENSE0X5B") (pin "2") (pinfunction "SCL_2") (pintype "bidirectional"))
      (node (ref "R5") (pin "2") (pinfunction "2_2") (pintype "passive"))
      (node (ref "U$1") (pin "29") (pinfunction "29/A18/SCL1_29") (pintype "bidirectional"))
    )
    (net (code "37") (name "/SD") (class "Default")
      (node (ref "R14") (pin "2") (pinfunction "2_2") (pintype "passive"))
      (node (ref "R15") (pin "2") (pinfunction "2_2") (pintype "passive"))
      (node (ref "U2") (pin "1") (pinfunction "/SD_1") (pintype "input"))
      (node (ref "U3") (pin "1") (pinfunction "/SD_1") (pintype "input"))
    )
    (net (code "38") (name "/SDA") (class "Default")
      (node (ref "CAPSENSE0X5A") (pin "3") (pinfunction "SDA_3") (pintype "bidirectional"))
      (node (ref "CAPSENSE0X5B") (pin "3") (pinfunction "SDA_3") (pintype "bidirectional"))
      (node (ref "R6") (pin "2") (pinfunction "2_2") (pintype "passive"))
      (node (ref "U$1") (pin "30") (pinfunction "30/A19/SDA1_30") (pintype "bidirectional"))
    )
    (net (code "39") (name "/SENS0A") (class "Default")
      (node (ref "FPCBOARD0") (pin "5") (pinfunction "5_5") (pintype "passive"))
      (node (ref "TORM0") (pin "2") (pinfunction "2_2") (pintype "passive"))
    )
    (net (code "40") (name "/SENS0B") (class "Default")
      (node (ref "CAPSENSE0X5B") (pin "8") (pinfunction "ELE0_8") (pintype "bidirectional"))
      (node (ref "FPCBOARD0") (pin "4") (pinfunction "4_4") (pintype "passive"))
    )
    (net (code "41") (name "/SENS0M") (class "Default")
      (node (ref "CAPSENSE0X5A") (pin "8") (pinfunction "ELE0_8") (pintype "bidirectional"))
      (node (ref "TORM0") (pin "1") (pinfunction "1_1") (pintype "passive"))
    )
    (net (code "42") (name "/SENS0T") (class "Default")
      (node (ref "TORM0") (pin "3") (pinfunction "3_3") (pintype "passive"))
      (node (ref "U$1") (pin "0") (pinfunction "0/RX1/T_0") (pintype "bidirectional"))
    )
    (net (code "43") (name "/SENS1A") (class "Default")
      (node (ref "FPCBOARD1") (pin "5") (pinfunction "5_5") (pintype "passive"))
      (node (ref "TORM1") (pin "2") (pinfunction "2_2") (pintype "passive"))
    )
    (net (code "44") (name "/SENS1B") (class "Default")
      (node (ref "CAPSENSE0X5B") (pin "9") (pinfunction "ELE1_9") (pintype "bidirectional"))
      (node (ref "FPCBOARD1") (pin "4") (pinfunction "4_4") (pintype "passive"))
    )
    (net (code "45") (name "/SENS1M") (class "Default")
      (node (ref "CAPSENSE0X5A") (pin "9") (pinfunction "ELE1_9") (pintype "bidirectional"))
      (node (ref "TORM1") (pin "1") (pinfunction "1_1") (pintype "passive"))
    )
    (net (code "46") (name "/SENS1T") (class "Default")
      (node (ref "TORM1") (pin "3") (pinfunction "3_3") (pintype "passive"))
      (node (ref "U$1") (pin "1") (pinfunction "1/TX1/T_1") (pintype "bidirectional"))
    )
    (net (code "47") (name "/SENS2A") (class "Default")
      (node (ref "FPCBOARD2") (pin "5") (pinfunction "5_5") (pintype "passive"))
      (node (ref "TORM2") (pin "2") (pinfunction "2_2") (pintype "passive"))
    )
    (net (code "48") (name "/SENS2B") (class "Default")
      (node (ref "CAPSENSE0X5B") (pin "10") (pinfunction "ELE2_10") (pintype "bidirectional"))
      (node (ref "FPCBOARD2") (pin "4") (pinfunction "4_4") (pintype "passive"))
    )
    (net (code "49") (name "/SENS2M") (class "Default")
      (node (ref "CAPSENSE0X5A") (pin "10") (pinfunction "ELE2_10") (pintype "bidirectional"))
      (node (ref "TORM2") (pin "1") (pinfunction "1_1") (pintype "passive"))
    )
    (net (code "50") (name "/SENS2T") (class "Default")
      (node (ref "TORM2") (pin "3") (pinfunction "3_3") (pintype "passive"))
      (node (ref "U$1") (pin "15/A1") (pinfunction "15/A1/T_15/A1") (pintype "bidirectional"))
    )
    (net (code "51") (name "/SENS3A") (class "Default")
      (node (ref "FPCBOARD3") (pin "5") (pinfunction "5_5") (pintype "passive"))
      (node (ref "TORM3") (pin "2") (pinfunction "2_2") (pintype "passive"))
    )
    (net (code "52") (name "/SENS3B") (class "Default")
      (node (ref "CAPSENSE0X5B") (pin "11") (pinfunction "ELE3_11") (pintype "bidirectional"))
      (node (ref "FPCBOARD3") (pin "4") (pinfunction "4_4") (pintype "passive"))
    )
    (net (code "53") (name "/SENS3M") (class "Default")
      (node (ref "CAPSENSE0X5A") (pin "11") (pinfunction "ELE3_11") (pintype "bidirectional"))
      (node (ref "TORM3") (pin "1") (pinfunction "1_1") (pintype "passive"))
    )
    (net (code "54") (name "/SENS3T") (class "Default")
      (node (ref "TORM3") (pin "3") (pinfunction "3_3") (pintype "passive"))
      (node (ref "U$1") (pin "16/A2") (pinfunction "16/A2/T_16/A2") (pintype "bidirectional"))
    )
    (net (code "55") (name "/SENS4A") (class "Default")
      (node (ref "FPCBOARD4") (pin "5") (pinfunction "5_5") (pintype "passive"))
      (node (ref "TORM4") (pin "2") (pinfunction "2_2") (pintype "passive"))
    )
    (net (code "56") (name "/SENS4B") (class "Default")
      (node (ref "CAPSENSE0X5B") (pin "12") (pinfunction "ELE4/LED0_12") (pintype "bidirectional"))
      (node (ref "FPCBOARD4") (pin "4") (pinfunction "4_4") (pintype "passive"))
    )
    (net (code "57") (name "/SENS4M") (class "Default")
      (node (ref "CAPSENSE0X5A") (pin "12") (pinfunction "ELE4/LED0_12") (pintype "bidirectional"))
      (node (ref "TORM4") (pin "1") (pinfunction "1_1") (pintype "passive"))
    )
    (net (code "58") (name "/SENS4T") (class "Default")
      (node (ref "TORM4") (pin "3") (pinfunction "3_3") (pintype "passive"))
      (node (ref "U$1") (pin "17/A3") (pinfunction "17/A3/T_17/A3") (pintype "bidirectional"))
    )
    (net (code "59") (name "/SENS5A") (class "Default")
      (node (ref "FPCBOARD5") (pin "5") (pinfunction "5_5") (pintype "passive"))
      (node (ref "TORM5") (pin "2") (pinfunction "2_2") (pintype "passive"))
    )
    (net (code "60") (name "/SENS5B") (class "Default")
      (node (ref "CAPSENSE0X5B") (pin "13") (pinfunction "ELE5/LED1_13") (pintype "bidirectional"))
      (node (ref "FPCBOARD5") (pin "4") (pinfunction "4_4") (pintype "passive"))
    )
    (net (code "61") (name "/SENS5M") (class "Default")
      (node (ref "CAPSENSE0X5A") (pin "13") (pinfunction "ELE5/LED1_13") (pintype "bidirectional"))
      (node (ref "TORM5") (pin "1") (pinfunction "1_1") (pintype "passive"))
    )
    (net (code "62") (name "/SENS5T") (class "Default")
      (node (ref "TORM5") (pin "3") (pinfunction "3_3") (pintype "passive"))
      (node (ref "U$1") (pin "18/A4") (pinfunction "18/A4/T/SDA0_18/A4") (pintype "bidirectional"))
    )
    (net (code "63") (name "/SENS6A") (class "Default")
      (node (ref "FPCBOARD6") (pin "5") (pinfunction "5_5") (pintype "passive"))
      (node (ref "TORM6") (pin "2") (pinfunction "2_2") (pintype "passive"))
    )
    (net (code "64") (name "/SENS6B") (class "Default")
      (node (ref "CAPSENSE0X5B") (pin "14") (pinfunction "ELE6/LED2_14") (pintype "bidirectional"))
      (node (ref "FPCBOARD6") (pin "4") (pinfunction "4_4") (pintype "passive"))
    )
    (net (code "65") (name "/SENS6M") (class "Default")
      (node (ref "CAPSENSE0X5A") (pin "14") (pinfunction "ELE6/LED2_14") (pintype "bidirectional"))
      (node (ref "TORM6") (pin "1") (pinfunction "1_1") (pintype "passive"))
    )
    (net (code "66") (name "/SENS6T") (class "Default")
      (node (ref "TORM6") (pin "3") (pinfunction "3_3") (pintype "passive"))
      (node (ref "U$1") (pin "19/A5") (pinfunction "19/A5/T/SCL0_19/A5") (pintype "bidirectional"))
    )
    (net (code "67") (name "/SENS7A") (class "Default")
      (node (ref "FPCBOARD7") (pin "5") (pinfunction "5_5") (pintype "passive"))
      (node (ref "TORM7") (pin "2") (pinfunction "2_2") (pintype "passive"))
    )
    (net (code "68") (name "/SENS7B") (class "Default")
      (node (ref "CAPSENSE0X5B") (pin "15") (pinfunction "ELE7/LED3_15") (pintype "bidirectional"))
      (node (ref "FPCBOARD7") (pin "4") (pinfunction "4_4") (pintype "passive"))
    )
    (net (code "69") (name "/SENS7M") (class "Default")
      (node (ref "CAPSENSE0X5A") (pin "15") (pinfunction "ELE7/LED3_15") (pintype "bidirectional"))
      (node (ref "TORM7") (pin "1") (pinfunction "1_1") (pintype "passive"))
    )
    (net (code "70") (name "/SENS7T") (class "Default")
      (node (ref "TORM7") (pin "3") (pinfunction "3_3") (pintype "passive"))
      (node (ref "U$1") (pin "22/A8") (pinfunction "22/A8/T/PWM_22/A8") (pintype "bidirectional"))
    )
    (net (code "71") (name "/SENS8A") (class "Default")
      (node (ref "FPCBOARD8") (pin "5") (pinfunction "5_5") (pintype "passive"))
      (node (ref "TORM8") (pin "2") (pinfunction "2_2") (pintype "passive"))
    )
    (net (code "72") (name "/SENS8B") (class "Default")
      (node (ref "CAPSENSE0X5B") (pin "16") (pinfunction "ELE8/LED4_16") (pintype "bidirectional"))
      (node (ref "FPCBOARD8") (pin "4") (pinfunction "4_4") (pintype "passive"))
    )
    (net (code "73") (name "/SENS8M") (class "Default")
      (node (ref "CAPSENSE0X5A") (pin "16") (pinfunction "ELE8/LED4_16") (pintype "bidirectional"))
      (node (ref "TORM8") (pin "1") (pinfunction "1_1") (pintype "passive"))
    )
    (net (code "74") (name "/SENS8T") (class "Default")
      (node (ref "TORM8") (pin "3") (pinfunction "3_3") (pintype "passive"))
      (node (ref "U$1") (pin "23/A9") (pinfunction "23/A9/T/PWM_23/A9") (pintype "bidirectional"))
    )
    (net (code "75") (name "/SENS9A") (class "Default")
      (node (ref "FPCBOARD9") (pin "5") (pinfunction "5_5") (pintype "passive"))
      (node (ref "TORM9") (pin "2") (pinfunction "2_2") (pintype "passive"))
    )
    (net (code "76") (name "/SENS9B") (class "Default")
      (node (ref "CAPSENSE0X5B") (pin "17") (pinfunction "ELE9/LED5_17") (pintype "bidirectional"))
      (node (ref "FPCBOARD9") (pin "4") (pinfunction "4_4") (pintype "passive"))
    )
    (net (code "77") (name "/SENS9M") (class "Default")
      (node (ref "CAPSENSE0X5A") (pin "17") (pinfunction "ELE9/LED5_17") (pintype "bidirectional"))
      (node (ref "TORM9") (pin "1") (pinfunction "1_1") (pintype "passive"))
    )
    (net (code "78") (name "/SENS9T") (class "Default")
      (node (ref "U$1") (pin "25") (pinfunction "25/T/PWM_25") (pintype "bidirectional"))
    )
    (net (code "79") (name "/SENS9T9") (class "Default")
      (node (ref "TORM9") (pin "3") (pinfunction "3_3") (pintype "passive"))
    )
    (net (code "80") (name "/SENS10A") (class "Default")
      (node (ref "FPCBOARD10") (pin "5") (pinfunction "5_5") (pintype "passive"))
      (node (ref "TORM10") (pin "2") (pinfunction "2_2") (pintype "passive"))
    )
    (net (code "81") (name "/SENS10B") (class "Default")
      (node (ref "CAPSENSE0X5B") (pin "18") (pinfunction "ELE10/LED6_18") (pintype "bidirectional"))
      (node (ref "FPCBOARD10") (pin "4") (pinfunction "4_4") (pintype "passive"))
    )
    (net (code "82") (name "/SENS10M") (class "Default")
      (node (ref "CAPSENSE0X5A") (pin "18") (pinfunction "ELE10/LED6_18") (pintype "bidirectional"))
      (node (ref "TORM10") (pin "1") (pinfunction "1_1") (pintype "passive"))
    )
    (net (code "83") (name "/SENS10T") (class "Default")
      (node (ref "TORM10") (pin "3") (pinfunction "3_3") (pintype "passive"))
      (node (ref "U$1") (pin "32") (pinfunction "32/T/PWM_32") (pintype "bidirectional"))
    )
    (net (code "84") (name "/SENS11A") (class "Default")
      (node (ref "FPCBOARD11") (pin "5") (pinfunction "5_5") (pintype "passive"))
      (node (ref "TORM11") (pin "2") (pinfunction "2_2") (pintype "passive"))
    )
    (net (code "85") (name "/SENS11B") (class "Default")
      (node (ref "CAPSENSE0X5B") (pin "19") (pinfunction "ELE11/LED7_19") (pintype "bidirectional"))
      (node (ref "FPCBOARD11") (pin "4") (pinfunction "4_4") (pintype "passive"))
    )
    (net (code "86") (name "/SENS11M") (class "Default")
      (node (ref "CAPSENSE0X5A") (pin "19") (pinfunction "ELE11/LED7_19") (pintype "bidirectional"))
      (node (ref "TORM11") (pin "1") (pinfunction "1_1") (pintype "passive"))
    )
    (net (code "87") (name "/SENS11T") (class "Default")
      (node (ref "TORM11") (pin "3") (pinfunction "3_3") (pintype "passive"))
      (node (ref "U$1") (pin "33") (pinfunction "33/T_33") (pintype "bidirectional"))
    )
    (net (code "88") (name "/TOUCHB0") (class "Default")
      (node (ref "FPCSENSOR0") (pin "3") (pinfunction "3_3") (pintype "passive"))
      (node (ref "TOUCHCHOOSE0") (pin "1") (pinfunction "1_1") (pintype "passive"))
    )
    (net (code "89") (name "/TOUCHPAD0") (class "Default")
      (node (ref "FPCSENSOR0") (pin "2") (pinfunction "2_2") (pintype "passive"))
      (node (ref "TOUCHCHOOSE0") (pin "3") (pinfunction "3_3") (pintype "passive"))
    )
    (net (code "90") (name "/TOUCHPAD1") (class "Default")
      (node (ref "FPCSENSOR1") (pin "2") (pinfunction "2_2") (pintype "passive"))
      (node (ref "TOUCHCHOOSE1") (pin "3") (pinfunction "3_3") (pintype "passive"))
    )
    (net (code "91") (name "/TOUCHPAD2") (class "Default")
      (node (ref "FPCSENSOR2") (pin "2") (pinfunction "2_2") (pintype "passive"))
      (node (ref "TOUCHCHOOSE2") (pin "3") (pinfunction "3_3") (pintype "passive"))
    )
    (net (code "92") (name "/TOUCHPAD3") (class "Default")
      (node (ref "FPCSENSOR3") (pin "2") (pinfunction "2_2") (pintype "passive"))
      (node (ref "TOUCHCHOOSE3") (pin "3") (pinfunction "3_3") (pintype "passive"))
    )
    (net (code "93") (name "/TOUCHPAD4") (class "Default")
      (node (ref "FPCSENSOR4") (pin "2") (pinfunction "2_2") (pintype "passive"))
      (node (ref "TOUCHCHOOSE4") (pin "3") (pinfunction "3_3") (pintype "passive"))
    )
    (net (code "94") (name "/TOUCHPAD5") (class "Default")
      (node (ref "FPCSENSOR5") (pin "2") (pinfunction "2_2") (pintype "passive"))
      (node (ref "TOUCHCHOOSE5") (pin "3") (pinfunction "3_3") (pintype "passive"))
    )
    (net (code "95") (name "/TOUCHPAD6") (class "Default")
      (node (ref "FPCSENSOR6") (pin "2") (pinfunction "2_2") (pintype "passive"))
      (node (ref "TOUCHCHOOSE6") (pin "3") (pinfunction "3_3") (pintype "passive"))
    )
    (net (code "96") (name "/TOUCHPAD7") (class "Default")
      (node (ref "FPCSENSOR7") (pin "2") (pinfunction "2_2") (pintype "passive"))
      (node (ref "TOUCHCHOOSE7") (pin "3") (pinfunction "3_3") (pintype "passive"))
    )
    (net (code "97") (name "/TOUCHPAD8") (class "Default")
      (node (ref "FPCSENSOR8") (pin "2") (pinfunction "2_2") (pintype "passive"))
      (node (ref "TOUCHCHOOSE8") (pin "3") (pinfunction "3_3") (pintype "passive"))
    )
    (net (code "98") (name "/TOUCHPAD9") (class "Default")
      (node (ref "FPCSENSOR9") (pin "2") (pinfunction "2_2") (pintype "passive"))
      (node (ref "TOUCHCHOOSE9") (pin "3") (pinfunction "3_3") (pintype "passive"))
    )
    (net (code "99") (name "/TOUCHPAD10") (class "Default")
      (node (ref "FPCSENSOR10") (pin "2") (pinfunction "2_2") (pintype "passive"))
      (node (ref "TOUCHCHOOSE10") (pin "3") (pinfunction "3_3") (pintype "passive"))
    )
    (net (code "100") (name "/TOUCHPAD11") (class "Default")
      (node (ref "FPCSENSOR11") (pin "2") (pinfunction "2_2") (pintype "passive"))
      (node (ref "TOUCHCHOOSE11") (pin "3") (pinfunction "3_3") (pintype "passive"))
    )
    (net (code "101") (name "/TOUCHPOINT0") (class "Default")
      (node (ref "TOUCH0") (pin "TP") (pinfunction "TP_TP") (pintype "input"))
      (node (ref "TOUCHCHOOSE0") (pin "2") (pinfunction "2_2") (pintype "passive"))
    )
    (net (code "102") (name "/TOUCHPOINT1") (class "Default")
      (node (ref "TOUCH1") (pin "TP") (pinfunction "TP_TP") (pintype "input"))
      (node (ref "TOUCHCHOOSE1") (pin "2") (pinfunction "2_2") (pintype "passive"))
    )
    (net (code "103") (name "/TOUCHPOINT2") (class "Default")
      (node (ref "TOUCH2") (pin "TP") (pinfunction "TP_TP") (pintype "input"))
      (node (ref "TOUCHCHOOSE2") (pin "2") (pinfunction "2_2") (pintype "passive"))
    )
    (net (code "104") (name "/TOUCHPOINT3") (class "Default")
      (node (ref "TOUCH3") (pin "TP") (pinfunction "TP_TP") (pintype "input"))
      (node (ref "TOUCHCHOOSE3") (pin "2") (pinfunction "2_2") (pintype "passive"))
    )
    (net (code "105") (name "/TOUCHPOINT4") (class "Default")
      (node (ref "TOUCH4") (pin "TP") (pinfunction "TP_TP") (pintype "input"))
      (node (ref "TOUCHCHOOSE4") (pin "2") (pinfunction "2_2") (pintype "passive"))
    )
    (net (code "106") (name "/TOUCHPOINT5") (class "Default")
      (node (ref "TOUCH5") (pin "TP") (pinfunction "TP_TP") (pintype "input"))
      (node (ref "TOUCHCHOOSE5") (pin "2") (pinfunction "2_2") (pintype "passive"))
    )
    (net (code "107") (name "/TOUCHPOINT6") (class "Default")
      (node (ref "TOUCH6") (pin "TP") (pinfunction "TP_TP") (pintype "input"))
      (node (ref "TOUCHCHOOSE6") (pin "2") (pinfunction "2_2") (pintype "passive"))
    )
    (net (code "108") (name "/TOUCHPOINT7") (class "Default")
      (node (ref "TOUCH7") (pin "TP") (pinfunction "TP_TP") (pintype "input"))
      (node (ref "TOUCHCHOOSE7") (pin "2") (pinfunction "2_2") (pintype "passive"))
    )
    (net (code "109") (name "/TOUCHPOINT8") (class "Default")
      (node (ref "TOUCH8") (pin "TP") (pinfunction "TP_TP") (pintype "input"))
      (node (ref "TOUCHCHOOSE8") (pin "2") (pinfunction "2_2") (pintype "passive"))
    )
    (net (code "110") (name "/TOUCHPOINT9") (class "Default")
      (node (ref "TOUCH9") (pin "TP") (pinfunction "TP_TP") (pintype "input"))
      (node (ref "TOUCHCHOOSE9") (pin "2") (pinfunction "2_2") (pintype "passive"))
    )
    (net (code "111") (name "/TOUCHPOINT10") (class "Default")
      (node (ref "TOUCH10") (pin "TP") (pinfunction "TP_TP") (pintype "input"))
      (node (ref "TOUCHCHOOSE10") (pin "2") (pinfunction "2_2") (pintype "passive"))
    )
    (net (code "112") (name "/TOUCHPOINT11") (class "Default")
      (node (ref "TOUCH11") (pin "TP") (pinfunction "TP_TP") (pintype "input"))
      (node (ref "TOUCHCHOOSE11") (pin "2") (pinfunction "2_2") (pintype "passive"))
    )
    (net (code "113") (name "/VBAT") (class "Default")
      (node (ref "U$1") (pin "VBAT") (pinfunction "VBAT_VBAT") (pintype "power_in"))
    )
    (net (code "114") (name "/VIN") (class "Default")
      (node (ref "U$1") (pin "VIN") (pinfunction "VIN_VIN") (pintype "power_in"))
    )
    (net (code "115") (name "/VO+") (class "Default")
      (node (ref "C29") (pin "1") (pinfunction "1_1") (pintype "passive"))
      (node (ref "C32") (pin "1") (pinfunction "1_1") (pintype "passive"))
      (node (ref "FB1") (pin "2") (pinfunction "P$2_2") (pintype "passive"))
      (node (ref "FB3") (pin "2") (pinfunction "P$2_2") (pintype "passive"))
      (node (ref "SPEAKER1") (pin "1") (pinfunction "1_1") (pintype "passive"))
      (node (ref "SPEAKER2") (pin "1") (pinfunction "1_1") (pintype "passive"))
    )
    (net (code "116") (name "/VO-") (class "Default")
      (node (ref "C28") (pin "1") (pinfunction "1_1") (pintype "passive"))
      (node (ref "C31") (pin "1") (pinfunction "1_1") (pintype "passive"))
      (node (ref "FB2") (pin "2") (pinfunction "P$2_2") (pintype "passive"))
      (node (ref "FB4") (pin "2") (pinfunction "P$2_2") (pintype "passive"))
      (node (ref "SPEAKER1") (pin "2") (pinfunction "2_2") (pintype "passive"))
      (node (ref "SPEAKER2") (pin "2") (pinfunction "2_2") (pintype "passive"))
    )
    (net (code "117") (name "3.3V") (class "Default")
      (node (ref "C13") (pin "1") (pinfunction "1_1") (pintype "passive"))
      (node (ref "C15") (pin "1") (pinfunction "1_1") (pintype "passive"))
      (node (ref "C17") (pin "2") (pinfunction "2_2") (pintype "passive"))
      (node (ref "C19") (pin "1") (pinfunction "1_1") (pintype "passive"))
      (node (ref "C20") (pin "2") (pinfunction "2_2") (pintype "passive"))
      (node (ref "C24") (pin "1") (pinfunction "1_1") (pintype "passive"))
      (node (ref "CAPSENSE0X5A") (pin "20") (pinfunction "VDD_20") (pintype "bidirectional"))
      (node (ref "CAPSENSE0X5B") (pin "20") (pinfunction "VDD_20") (pintype "bidirectional"))
      (node (ref "CAPSENSE0X5B") (pin "4") (pinfunction "ADDR_4") (pintype "bidirectional"))
      (node (ref "DEMP") (pin "3") (pinfunction "3_3") (pintype "passive"))
      (node (ref "LATENCY") (pin "3") (pinfunction "3_3") (pintype "passive"))
      (node (ref "R3") (pin "1") (pinfunction "1_1") (pintype "passive"))
      (node (ref "R4") (pin "1") (pinfunction "1_1") (pintype "passive"))
      (node (ref "R5") (pin "1") (pinfunction "1_1") (pintype "passive"))
      (node (ref "R6") (pin "1") (pinfunction "1_1") (pintype "passive"))
      (node (ref "U$1") (pin "3.3V") (pinfunction "3.3V_3.3V") (pintype "power_in"))
      (node (ref "U$1") (pin "3.3V1") (pinfunction "3.3V_3.3V1") (pintype "power_in"))
      (node (ref "U$1") (pin "3.3V2") (pinfunction "3.3V_3.3V2") (pintype "power_in"))
      (node (ref "U1") (pin "1") (pinfunction "CPVDD_1") (pintype "power_in"))
      (node (ref "U1") (pin "20") (pinfunction "DVDD_20") (pintype "power_in"))
      (node (ref "U1") (pin "8") (pinfunction "AVDD_8") (pintype "power_in"))
      (node (ref "U5") (pin "3") (pinfunction "~{WP(D2})_3") (pintype "bidirectional"))
      (node (ref "U5") (pin "7") (pinfunction "~{HOLD(D3})_7") (pintype "bidirectional"))
      (node (ref "U5") (pin "8") (pinfunction "VCC_8") (pintype "bidirectional"))
      (node (ref "VR1") (pin "P$3") (pinfunction "A_P$3") (pintype "passive"))
    )
    (net (code "118") (name "5V") (class "Default")
      (node (ref "FPCBOARD0") (pin "2") (pinfunction "2_2") (pintype "passive"))
      (node (ref "FPCBOARD1") (pin "2") (pinfunction "2_2") (pintype "passive"))
      (node (ref "FPCBOARD10") (pin "2") (pinfunction "2_2") (pintype "passive"))
      (node (ref "FPCBOARD11") (pin "2") (pinfunction "2_2") (pintype "passive"))
      (node (ref "FPCBOARD2") (pin "2") (pinfunction "2_2") (pintype "passive"))
      (node (ref "FPCBOARD3") (pin "2") (pinfunction "2_2") (pintype "passive"))
      (node (ref "FPCBOARD4") (pin "2") (pinfunction "2_2") (pintype "passive"))
      (node (ref "FPCBOARD5") (pin "2") (pinfunction "2_2") (pintype "passive"))
      (node (ref "FPCBOARD6") (pin "2") (pinfunction "2_2") (pintype "passive"))
      (node (ref "FPCBOARD7") (pin "2") (pinfunction "2_2") (pintype "passive"))
      (node (ref "FPCBOARD8") (pin "2") (pinfunction "2_2") (pintype "passive"))
      (node (ref "FPCBOARD9") (pin "2") (pinfunction "2_2") (pintype "passive"))
      (node (ref "S2") (pin "2") (pinfunction "P_2") (pintype "passive"))
      (node (ref "U$1") (pin "VUSB") (pinfunction "VUSB_VUSB") (pintype "power_in"))
    )
    (net (code "119") (name "GND") (class "Default")
      (node (ref "C13") (pin "2") (pinfunction "2_2") (pintype "passive"))
      (node (ref "C14") (pin "2") (pinfunction "2_2") (pintype "passive"))
      (node (ref "C15") (pin "2") (pinfunction "2_2") (pintype "passive"))
      (node (ref "C16") (pin "2") (pinfunction "2_2") (pintype "passive"))
      (node (ref "C17") (pin "1") (pinfunction "1_1") (pintype "passive"))
      (node (ref "C18") (pin "2") (pinfunction "2_2") (pintype "passive"))
      (node (ref "C20") (pin "1") (pinfunction "1_1") (pintype "passive"))
      (node (ref "C21") (pin "2") (pinfunction "2_2") (pintype "passive"))
      (node (ref "C23") (pin "2") (pinfunction "2_2") (pintype "passive"))
      (node (ref "C24") (pin "2") (pinfunction "2_2") (pintype "passive"))
      (node (ref "C27") (pin "2") (pinfunction "2_2") (pintype "passive"))
      (node (ref "C28") (pin "2") (pinfunction "2_2") (pintype "passive"))
      (node (ref "C29") (pin "2") (pinfunction "2_2") (pintype "passive"))
      (node (ref "C30") (pin "2") (pinfunction "2_2") (pintype "passive"))
      (node (ref "C31") (pin "2") (pinfunction "2_2") (pintype "passive"))
      (node (ref "C32") (pin "2") (pinfunction "2_2") (pintype "passive"))
      (node (ref "CAPSENSE0X5A") (pin "4") (pinfunction "ADDR_4") (pintype "bidirectional"))
      (node (ref "CAPSENSE0X5A") (pin "6") (pinfunction "VSS_6") (pintype "bidirectional"))
      (node (ref "CAPSENSE0X5B") (pin "6") (pinfunction "VSS_6") (pintype "bidirectional"))
      (node (ref "DEMP") (pin "1") (pinfunction "1_1") (pintype "passive"))
      (node (ref "FPCBOARD0") (pin "1") (pinfunction "1_1") (pintype "passive"))
      (node (ref "FPCBOARD0") (pin "6") (pinfunction "6_6") (pintype "passive"))
      (node (ref "FPCBOARD0") (pin "S1") (pinfunction "SHIELD_S1") (pintype "passive"))
      (node (ref "FPCBOARD0") (pin "S2") (pinfunction "SHIELD_S2") (pintype "passive"))
      (node (ref "FPCBOARD1") (pin "1") (pinfunction "1_1") (pintype "passive"))
      (node (ref "FPCBOARD1") (pin "6") (pinfunction "6_6") (pintype "passive"))
      (node (ref "FPCBOARD1") (pin "S1") (pinfunction "SHIELD_S1") (pintype "passive"))
      (node (ref "FPCBOARD1") (pin "S2") (pinfunction "SHIELD_S2") (pintype "passive"))
      (node (ref "FPCBOARD10") (pin "1") (pinfunction "1_1") (pintype "passive"))
      (node (ref "FPCBOARD10") (pin "6") (pinfunction "6_6") (pintype "passive"))
      (node (ref "FPCBOARD10") (pin "S1") (pinfunction "SHIELD_S1") (pintype "passive"))
      (node (ref "FPCBOARD10") (pin "S2") (pinfunction "SHIELD_S2") (pintype "passive"))
      (node (ref "FPCBOARD11") (pin "1") (pinfunction "1_1") (pintype "passive"))
      (node (ref "FPCBOARD11") (pin "6") (pinfunction "6_6") (pintype "passive"))
      (node (ref "FPCBOARD11") (pin "S1") (pinfunction "SHIELD_S1") (pintype "passive"))
      (node (ref "FPCBOARD11") (pin "S2") (pinfunction "SHIELD_S2") (pintype "passive"))
      (node (ref "FPCBOARD2") (pin "1") (pinfunction "1_1") (pintype "passive"))
      (node (ref "FPCBOARD2") (pin "6") (pinfunction "6_6") (pintype "passive"))
      (node (ref "FPCBOARD2") (pin "S1") (pinfunction "SHIELD_S1") (pintype "passive"))
      (node (ref "FPCBOARD2") (pin "S2") (pinfunction "SHIELD_S2") (pintype "passive"))
      (node (ref "FPCBOARD3") (pin "1") (pinfunction "1_1") (pintype "passive"))
      (node (ref "FPCBOARD3") (pin "6") (pinfunction "6_6") (pintype "passive"))
      (node (ref "FPCBOARD3") (pin "S1") (pinfunction "SHIELD_S1") (pintype "passive"))
      (node (ref "FPCBOARD3") (pin "S2") (pinfunction "SHIELD_S2") (pintype "passive"))
      (node (ref "FPCBOARD4") (pin "1") (pinfunction "1_1") (pintype "passive"))
      (node (ref "FPCBOARD4") (pin "6") (pinfunction "6_6") (pintype "passive"))
      (node (ref "FPCBOARD4") (pin "S1") (pinfunction "SHIELD_S1") (pintype "passive"))
      (node (ref "FPCBOARD4") (pin "S2") (pinfunction "SHIELD_S2") (pintype "passive"))
      (node (ref "FPCBOARD5") (pin "1") (pinfunction "1_1") (pintype "passive"))
      (node (ref "FPCBOARD5") (pin "6") (pinfunction "6_6") (pintype "passive"))
      (node (ref "FPCBOARD5") (pin "S1") (pinfunction "SHIELD_S1") (pintype "passive"))
      (node (ref "FPCBOARD5") (pin "S2") (pinfunction "SHIELD_S2") (pintype "passive"))
      (node (ref "FPCBOARD6") (pin "1") (pinfunction "1_1") (pintype "passive"))
      (node (ref "FPCBOARD6") (pin "6") (pinfunction "6_6") (pintype "passive"))
      (node (ref "FPCBOARD6") (pin "S1") (pinfunction "SHIELD_S1") (pintype "passive"))
      (node (ref "FPCBOARD6") (pin "S2") (pinfunction "SHIELD_S2") (pintype "passive"))
      (node (ref "FPCBOARD7") (pin "1") (pinfunction "1_1") (pintype "passive"))
      (node (ref "FPCBOARD7") (pin "6") (pinfunction "6_6") (pintype "passive"))
      (node (ref "FPCBOARD7") (pin "S1") (pinfunction "SHIELD_S1") (pintype "passive"))
      (node (ref "FPCBOARD7") (pin "S2") (pinfunction "SHIELD_S2") (pintype "passive"))
      (node (ref "FPCBOARD8") (pin "1") (pinfunction "1_1") (pintype "passive"))
      (node (ref "FPCBOARD8") (pin "6") (pinfunction "6_6") (pintype "passive"))
      (node (ref "FPCBOARD8") (pin "S1") (pinfunction "SHIELD_S1") (pintype "passive"))
      (node (ref "FPCBOARD8") (pin "S2") (pinfunction "SHIELD_S2") (pintype "passive"))
      (node (ref "FPCBOARD9") (pin "1") (pinfunction "1_1") (pintype "passive"))
      (node (ref "FPCBOARD9") (pin "6") (pinfunction "6_6") (pintype "passive"))
      (node (ref "FPCBOARD9") (pin "S1") (pinfunction "SHIELD_S1") (pintype "passive"))
      (node (ref "FPCBOARD9") (pin "S2") (pinfunction "SHIELD_S2") (pintype "passive"))
      (node (ref "J4") (pin "1") (pinfunction "MIC_1") (pintype "bidirectional"))
      (node (ref "J4") (pin "2") (pinfunction "GND_2") (pintype "bidirectional"))
      (node (ref "LATENCY") (pin "1") (pinfunction "1_1") (pintype "passive"))
      (node (ref "R1") (pin "1") (pinfunction "1_1") (pintype "passive"))
      (node (ref "R2") (pin "1") (pinfunction "1_1") (pintype "passive"))
      (node (ref "S1") (pin "C") (pinfunction "C_C") (pintype "bidirectional"))
      (node (ref "S1") (pin "SW-") (pinfunction "SW-_SW-") (pintype "bidirectional"))
      (node (ref "S2") (pin "B") (pinfunction "B_B") (pintype "passive"))
      (node (ref "U$1") (pin "GND") (pinfunction "GND_GND") (pintype "power_in"))
      (node (ref "U$1") (pin "GND1") (pinfunction "GND_GND1") (pintype "power_in"))
      (node (ref "U$1") (pin "GND2") (pinfunction "GND_GND2") (pintype "power_in"))
      (node (ref "U1") (pin "12") (pinfunction "SCK_12") (pintype "input"))
      (node (ref "U1") (pin "16") (pinfunction "FMT_16") (pintype "input"))
      (node (ref "U1") (pin "19") (pinfunction "DGND_19") (pintype "power_in"))
      (node (ref "U1") (pin "3") (pinfunction "CPGND_3") (pintype "power_in"))
      (node (ref "U1") (pin "9") (pinfunction "AGND_9") (pintype "power_in"))
      (node (ref "U2") (pin "4") (pinfunction "IN_N_4") (pintype "input"))
      (node (ref "U2") (pin "7") (pinfunction "GND_7") (pintype "power_in"))
      (node (ref "U3") (pin "4") (pinfunction "IN_N_4") (pintype "input"))
      (node (ref "U3") (pin "7") (pinfunction "GND_7") (pintype "power_in"))
      (node (ref "U5") (pin "4") (pinfunction "GND_4") (pintype "bidirectional"))
      (node (ref "VR1") (pin "P$1") (pinfunction "E_P$1") (pintype "passive"))
    )
    (net (code "120") (name "Net-(C25-Pad1)") (class "Default")
      (node (ref "C25") (pin "1") (pinfunction "1_1") (pintype "passive"))
      (node (ref "R13") (pin "1") (pinfunction "1_1") (pintype "passive"))
    )
    (net (code "121") (name "Net-(C26-Pad1)") (class "Default")
      (node (ref "C26") (pin "1") (pinfunction "1_1") (pintype "passive"))
      (node (ref "R12") (pin "1") (pinfunction "1_1") (pintype "passive"))
    )
    (net (code "122") (name "Net-(CAPSENSE0X5A-REXT)") (class "Default")
      (node (ref "CAPSENSE0X5A") (pin "7") (pinfunction "REXT_7") (pintype "bidirectional"))
      (node (ref "R1") (pin "2") (pinfunction "2_2") (pintype "passive"))
    )
    (net (code "123") (name "Net-(CAPSENSE0X5A-VREG)") (class "Default")
      (node (ref "C14") (pin "1") (pinfunction "1_1") (pintype "passive"))
      (node (ref "CAPSENSE0X5A") (pin "5") (pinfunction "VREG_5") (pintype "bidirectional"))
    )
    (net (code "124") (name "Net-(CAPSENSE0X5B-REXT)") (class "Default")
      (node (ref "CAPSENSE0X5B") (pin "7") (pinfunction "REXT_7") (pintype "bidirectional"))
      (node (ref "R2") (pin "2") (pinfunction "2_2") (pintype "passive"))
    )
    (net (code "125") (name "Net-(CAPSENSE0X5B-VREG)") (class "Default")
      (node (ref "C16") (pin "1") (pinfunction "1_1") (pintype "passive"))
      (node (ref "CAPSENSE0X5B") (pin "5") (pinfunction "VREG_5") (pintype "bidirectional"))
    )
    (net (code "126") (name "Net-(FB1-P$1)") (class "Default")
      (node (ref "FB1") (pin "1") (pinfunction "P$1_1") (pintype "passive"))
      (node (ref "U2") (pin "5") (pinfunction "VO_P_5") (pintype "output"))
    )
    (net (code "127") (name "Net-(FB2-P$1)") (class "Default")
      (node (ref "FB2") (pin "1") (pinfunction "P$1_1") (pintype "passive"))
      (node (ref "U2") (pin "8") (pinfunction "VO_N_8") (pintype "output"))
    )
    (net (code "128") (name "Net-(FB3-P$1)") (class "Default")
      (node (ref "FB3") (pin "1") (pinfunction "P$1_1") (pintype "passive"))
      (node (ref "U3") (pin "5") (pinfunction "VO_P_5") (pintype "output"))
    )
    (net (code "129") (name "Net-(FB4-P$1)") (class "Default")
      (node (ref "FB4") (pin "1") (pinfunction "P$1_1") (pintype "passive"))
      (node (ref "U3") (pin "8") (pinfunction "VO_N_8") (pintype "output"))
    )
    (net (code "130") (name "Net-(FPCSENSOR1-Pad3)") (class "Default")
      (node (ref "FPCSENSOR1") (pin "3") (pinfunction "3_3") (pintype "passive"))
      (node (ref "TOUCHCHOOSE1") (pin "1") (pinfunction "1_1") (pintype "passive"))
    )
    (net (code "131") (name "Net-(FPCSENSOR2-Pad3)") (class "Default")
      (node (ref "FPCSENSOR2") (pin "3") (pinfunction "3_3") (pintype "passive"))
      (node (ref "TOUCHCHOOSE2") (pin "1") (pinfunction "1_1") (pintype "passive"))
    )
    (net (code "132") (name "Net-(FPCSENSOR3-Pad3)") (class "Default")
      (node (ref "FPCSENSOR3") (pin "3") (pinfunction "3_3") (pintype "passive"))
      (node (ref "TOUCHCHOOSE3") (pin "1") (pinfunction "1_1") (pintype "passive"))
    )
    (net (code "133") (name "Net-(FPCSENSOR4-Pad3)") (class "Default")
      (node (ref "FPCSENSOR4") (pin "3") (pinfunction "3_3") (pintype "passive"))
      (node (ref "TOUCHCHOOSE4") (pin "1") (pinfunction "1_1") (pintype "passive"))
    )
    (net (code "134") (name "Net-(FPCSENSOR5-Pad3)") (class "Default")
      (node (ref "FPCSENSOR5") (pin "3") (pinfunction "3_3") (pintype "passive"))
      (node (ref "TOUCHCHOOSE5") (pin "1") (pinfunction "1_1") (pintype "passive"))
    )
    (net (code "135") (name "Net-(FPCSENSOR6-Pad3)") (class "Default")
      (node (ref "FPCSENSOR6") (pin "3") (pinfunction "3_3") (pintype "passive"))
      (node (ref "TOUCHCHOOSE6") (pin "1") (pinfunction "1_1") (pintype "passive"))
    )
    (net (code "136") (name "Net-(FPCSENSOR7-Pad3)") (class "Default")
      (node (ref "FPCSENSOR7") (pin "3") (pinfunction "3_3") (pintype "passive"))
      (node (ref "TOUCHCHOOSE7") (pin "1") (pinfunction "1_1") (pintype "passive"))
    )
    (net (code "137") (name "Net-(FPCSENSOR8-Pad3)") (class "Default")
      (node (ref "FPCSENSOR8") (pin "3") (pinfunction "3_3") (pintype "passive"))
      (node (ref "TOUCHCHOOSE8") (pin "1") (pinfunction "1_1") (pintype "passive"))
    )
    (net (code "138") (name "Net-(FPCSENSOR9-Pad3)") (class "Default")
      (node (ref "FPCSENSOR9") (pin "3") (pinfunction "3_3") (pintype "passive"))
      (node (ref "TOUCHCHOOSE9") (pin "1") (pinfunction "1_1") (pintype "passive"))
    )
    (net (code "139") (name "Net-(FPCSENSOR10-Pad3)") (class "Default")
      (node (ref "FPCSENSOR10") (pin "3") (pinfunction "3_3") (pintype "passive"))
      (node (ref "TOUCHCHOOSE10") (pin "1") (pinfunction "1_1") (pintype "passive"))
    )
    (net (code "140") (name "Net-(FPCSENSOR11-Pad3)") (class "Default")
      (node (ref "FPCSENSOR11") (pin "3") (pinfunction "3_3") (pintype "passive"))
      (node (ref "TOUCHCHOOSE11") (pin "1") (pinfunction "1_1") (pintype "passive"))
    )
    (net (code "141") (name "Net-(J3-PadGND)") (class "Default")
      (node (ref "J3") (pin "GND") (pinfunction "GND_GND") (pintype "power_in"))
      (node (ref "J3") (pin "SHLD1") (pinfunction "SHIELD_SHLD1") (pintype "bidirectional"))
      (node (ref "J3") (pin "SHLD2") (pinfunction "SHIELD_SHLD2") (pintype "bidirectional"))
      (node (ref "S2") (pin "B1") (pinfunction "B1_B1") (pintype "passive"))
    )
    (net (code "142") (name "Net-(LED0-DI)") (class "Default")
      (node (ref "FPCSENSOR0") (pin "4") (pinfunction "4_4") (pintype "passive"))
      (node (ref "LED0") (pin "4") (pinfunction "DI_4") (pintype "bidirectional"))
    )
    (net (code "143") (name "Net-(LED0-VDD)") (class "Default")
      (node (ref "C1") (pin "2") (pinfunction "2_2") (pintype "passive"))
      (node (ref "FPCSENSOR0") (pin "5") (pinfunction "5_5") (pintype "passive"))
      (node (ref "LED0") (pin "1") (pinfunction "VDD_1") (pintype "bidirectional"))
    )
    (net (code "144") (name "Net-(LED0-VSS)") (class "Default")
      (node (ref "C1") (pin "1") (pinfunction "1_1") (pintype "passive"))
      (node (ref "FPCSENSOR0") (pin "1") (pinfunction "1_1") (pintype "passive"))
      (node (ref "FPCSENSOR0") (pin "6") (pinfunction "6_6") (pintype "passive"))
      (node (ref "FPCSENSOR0") (pin "S1") (pinfunction "SHIELD_S1") (pintype "passive"))
      (node (ref "FPCSENSOR0") (pin "S2") (pinfunction "SHIELD_S2") (pintype "passive"))
      (node (ref "LED0") (pin "3") (pinfunction "VSS_3") (pintype "bidirectional"))
    )
    (net (code "145") (name "Net-(LED1-DI)") (class "Default")
      (node (ref "FPCSENSOR1") (pin "4") (pinfunction "4_4") (pintype "passive"))
      (node (ref "LED1") (pin "4") (pinfunction "DI_4") (pintype "bidirectional"))
    )
    (net (code "146") (name "Net-(LED1-VDD)") (class "Default")
      (node (ref "C2") (pin "2") (pinfunction "2_2") (pintype "passive"))
      (node (ref "FPCSENSOR1") (pin "5") (pinfunction "5_5") (pintype "passive"))
      (node (ref "LED1") (pin "1") (pinfunction "VDD_1") (pintype "bidirectional"))
    )
    (net (code "147") (name "Net-(LED1-VSS)") (class "Default")
      (node (ref "C2") (pin "1") (pinfunction "1_1") (pintype "passive"))
      (node (ref "FPCSENSOR1") (pin "1") (pinfunction "1_1") (pintype "passive"))
      (node (ref "FPCSENSOR1") (pin "6") (pinfunction "6_6") (pintype "passive"))
      (node (ref "FPCSENSOR1") (pin "S1") (pinfunction "SHIELD_S1") (pintype "passive"))
      (node (ref "FPCSENSOR1") (pin "S2") (pinfunction "SHIELD_S2") (pintype "passive"))
      (node (ref "LED1") (pin "3") (pinfunction "VSS_3") (pintype "bidirectional"))
    )
    (net (code "148") (name "Net-(LED2-DI)") (class "Default")
      (node (ref "FPCSENSOR2") (pin "4") (pinfunction "4_4") (pintype "passive"))
      (node (ref "LED2") (pin "4") (pinfunction "DI_4") (pintype "bidirectional"))
    )
    (net (code "149") (name "Net-(LED2-VDD)") (class "Default")
      (node (ref "C3") (pin "2") (pinfunction "2_2") (pintype "passive"))
      (node (ref "FPCSENSOR2") (pin "5") (pinfunction "5_5") (pintype "passive"))
      (node (ref "LED2") (pin "1") (pinfunction "VDD_1") (pintype "bidirectional"))
    )
    (net (code "150") (name "Net-(LED2-VSS)") (class "Default")
      (node (ref "C3") (pin "1") (pinfunction "1_1") (pintype "passive"))
      (node (ref "FPCSENSOR2") (pin "1") (pinfunction "1_1") (pintype "passive"))
      (node (ref "FPCSENSOR2") (pin "6") (pinfunction "6_6") (pintype "passive"))
      (node (ref "FPCSENSOR2") (pin "S1") (pinfunction "SHIELD_S1") (pintype "passive"))
      (node (ref "FPCSENSOR2") (pin "S2") (pinfunction "SHIELD_S2") (pintype "passive"))
      (node (ref "LED2") (pin "3") (pinfunction "VSS_3") (pintype "bidirectional"))
    )
    (net (code "151") (name "Net-(LED3-DI)") (class "Default")
      (node (ref "FPCSENSOR3") (pin "4") (pinfunction "4_4") (pintype "passive"))
      (node (ref "LED3") (pin "4") (pinfunction "DI_4") (pintype "bidirectional"))
    )
    (net (code "152") (name "Net-(LED3-VDD)") (class "Default")
      (node (ref "C4") (pin "2") (pinfunction "2_2") (pintype "passive"))
      (node (ref "FPCSENSOR3") (pin "5") (pinfunction "5_5") (pintype "passive"))
      (node (ref "LED3") (pin "1") (pinfunction "VDD_1") (pintype "bidirectional"))
    )
    (net (code "153") (name "Net-(LED3-VSS)") (class "Default")
      (node (ref "C4") (pin "1") (pinfunction "1_1") (pintype "passive"))
      (node (ref "FPCSENSOR3") (pin "1") (pinfunction "1_1") (pintype "passive"))
      (node (ref "FPCSENSOR3") (pin "6") (pinfunction "6_6") (pintype "passive"))
      (node (ref "FPCSENSOR3") (pin "S1") (pinfunction "SHIELD_S1") (pintype "passive"))
      (node (ref "FPCSENSOR3") (pin "S2") (pinfunction "SHIELD_S2") (pintype "passive"))
      (node (ref "LED3") (pin "3") (pinfunction "VSS_3") (pintype "bidirectional"))
    )
    (net (code "154") (name "Net-(LED4-DI)") (class "Default")
      (node (ref "FPCSENSOR4") (pin "4") (pinfunction "4_4") (pintype "passive"))
      (node (ref "LED4") (pin "4") (pinfunction "DI_4") (pintype "bidirectional"))
    )
    (net (code "155") (name "Net-(LED4-VDD)") (class "Default")
      (node (ref "C5") (pin "2") (pinfunction "2_2") (pintype "passive"))
      (node (ref "FPCSENSOR4") (pin "5") (pinfunction "5_5") (pintype "passive"))
      (node (ref "LED4") (pin "1") (pinfunction "VDD_1") (pintype "bidirectional"))
    )
    (net (code "156") (name "Net-(LED4-VSS)") (class "Default")
      (node (ref "C5") (pin "1") (pinfunction "1_1") (pintype "passive"))
      (node (ref "FPCSENSOR4") (pin "1") (pinfunction "1_1") (pintype "passive"))
      (node (ref "FPCSENSOR4") (pin "6") (pinfunction "6_6") (pintype "passive"))
      (node (ref "FPCSENSOR4") (pin "S1") (pinfunction "SHIELD_S1") (pintype "passive"))
      (node (ref "FPCSENSOR4") (pin "S2") (pinfunction "SHIELD_S2") (pintype "passive"))
      (node (ref "LED4") (pin "3") (pinfunction "VSS_3") (pintype "bidirectional"))
    )
    (net (code "157") (name "Net-(LED5-DI)") (class "Default")
      (node (ref "FPCSENSOR5") (pin "4") (pinfunction "4_4") (pintype "passive"))
      (node (ref "LED5") (pin "4") (pinfunction "DI_4") (pintype "bidirectional"))
    )
    (net (code "158") (name "Net-(LED5-VDD)") (class "Default")
      (node (ref "C6") (pin "2") (pinfunction "2_2") (pintype "passive"))
      (node (ref "FPCSENSOR5") (pin "5") (pinfunction "5_5") (pintype "passive"))
      (node (ref "LED5") (pin "1") (pinfunction "VDD_1") (pintype "bidirectional"))
    )
    (net (code "159") (name "Net-(LED5-VSS)") (class "Default")
      (node (ref "C6") (pin "1") (pinfunction "1_1") (pintype "passive"))
      (node (ref "FPCSENSOR5") (pin "1") (pinfunction "1_1") (pintype "passive"))
      (node (ref "FPCSENSOR5") (pin "6") (pinfunction "6_6") (pintype "passive"))
      (node (ref "FPCSENSOR5") (pin "S1") (pinfunction "SHIELD_S1") (pintype "passive"))
      (node (ref "FPCSENSOR5") (pin "S2") (pinfunction "SHIELD_S2") (pintype "passive"))
      (node (ref "LED5") (pin "3") (pinfunction "VSS_3") (pintype "bidirectional"))
    )
    (net (code "160") (name "Net-(LED6-DI)") (class "Default")
      (node (ref "FPCSENSOR6") (pin "4") (pinfunction "4_4") (pintype "passive"))
      (node (ref "LED6") (pin "4") (pinfunction "DI_4") (pintype "bidirectional"))
    )
    (net (code "161") (name "Net-(LED6-VDD)") (class "Default")
      (node (ref "C7") (pin "2") (pinfunction "2_2") (pintype "passive"))
      (node (ref "FPCSENSOR6") (pin "5") (pinfunction "5_5") (pintype "passive"))
      (node (ref "LED6") (pin "1") (pinfunction "VDD_1") (pintype "bidirectional"))
    )
    (net (code "162") (name "Net-(LED6-VSS)") (class "Default")
      (node (ref "C7") (pin "1") (pinfunction "1_1") (pintype "passive"))
      (node (ref "FPCSENSOR6") (pin "1") (pinfunction "1_1") (pintype "passive"))
      (node (ref "FPCSENSOR6") (pin "6") (pinfunction "6_6") (pintype "passive"))
      (node (ref "FPCSENSOR6") (pin "S1") (pinfunction "SHIELD_S1") (pintype "passive"))
      (node (ref "FPCSENSOR6") (pin "S2") (pinfunction "SHIELD_S2") (pintype "passive"))
      (node (ref "LED6") (pin "3") (pinfunction "VSS_3") (pintype "bidirectional"))
    )
    (net (code "163") (name "Net-(LED7-DI)") (class "Default")
      (node (ref "FPCSENSOR7") (pin "4") (pinfunction "4_4") (pintype "passive"))
      (node (ref "LED7") (pin "4") (pinfunction "DI_4") (pintype "bidirectional"))
    )
    (net (code "164") (name "Net-(LED7-VDD)") (class "Default")
      (node (ref "C8") (pin "2") (pinfunction "2_2") (pintype "passive"))
      (node (ref "FPCSENSOR7") (pin "5") (pinfunction "5_5") (pintype "passive"))
      (node (ref "LED7") (pin "1") (pinfunction "VDD_1") (pintype "bidirectional"))
    )
    (net (code "165") (name "Net-(LED7-VSS)") (class "Default")
      (node (ref "C8") (pin "1") (pinfunction "1_1") (pintype "passive"))
      (node (ref "FPCSENSOR7") (pin "1") (pinfunction "1_1") (pintype "passive"))
      (node (ref "FPCSENSOR7") (pin "6") (pinfunction "6_6") (pintype "passive"))
      (node (ref "FPCSENSOR7") (pin "S1") (pinfunction "SHIELD_S1") (pintype "passive"))
      (node (ref "FPCSENSOR7") (pin "S2") (pinfunction "SHIELD_S2") (pintype "passive"))
      (node (ref "LED7") (pin "3") (pinfunction "VSS_3") (pintype "bidirectional"))
    )
    (net (code "166") (name "Net-(LED8-DI)") (class "Default")
      (node (ref "FPCSENSOR8") (pin "4") (pinfunction "4_4") (pintype "passive"))
      (node (ref "LED8") (pin "4") (pinfunction "DI_4") (pintype "bidirectional"))
    )
    (net (code "167") (name "Net-(LED8-VDD)") (class "Default")
      (node (ref "C9") (pin "2") (pinfunction "2_2") (pintype "passive"))
      (node (ref "FPCSENSOR8") (pin "5") (pinfunction "5_5") (pintype "passive"))
      (node (ref "LED8") (pin "1") (pinfunction "VDD_1") (pintype "bidirectional"))
    )
    (net (code "168") (name "Net-(LED8-VSS)") (class "Default")
      (node (ref "C9") (pin "1") (pinfunction "1_1") (pintype "passive"))
      (node (ref "FPCSENSOR8") (pin "1") (pinfunction "1_1") (pintype "passive"))
      (node (ref "FPCSENSOR8") (pin "6") (pinfunction "6_6") (pintype "passive"))
      (node (ref "FPCSENSOR8") (pin "S1") (pinfunction "SHIELD_S1") (pintype "passive"))
      (node (ref "FPCSENSOR8") (pin "S2") (pinfunction "SHIELD_S2") (pintype "passive"))
      (node (ref "LED8") (pin "3") (pinfunction "VSS_3") (pintype "bidirectional"))
    )
    (net (code "169") (name "Net-(LED9-DI)") (class "Default")
      (node (ref "FPCSENSOR9") (pin "4") (pinfunction "4_4") (pintype "passive"))
      (node (ref "LED9") (pin "4") (pinfunction "DI_4") (pintype "bidirectional"))
    )
    (net (code "170") (name "Net-(LED9-VDD)") (class "Default")
      (node (ref "C10") (pin "2") (pinfunction "2_2") (pintype "passive"))
      (node (ref "FPCSENSOR9") (pin "5") (pinfunction "5_5") (pintype "passive"))
      (node (ref "LED9") (pin "1") (pinfunction "VDD_1") (pintype "bidirectional"))
    )
    (net (code "171") (name "Net-(LED9-VSS)") (class "Default")
      (node (ref "C10") (pin "1") (pinfunction "1_1") (pintype "passive"))
      (node (ref "FPCSENSOR9") (pin "1") (pinfunction "1_1") (pintype "passive"))
      (node (ref "FPCSENSOR9") (pin "6") (pinfunction "6_6") (pintype "passive"))
      (node (ref "FPCSENSOR9") (pin "S1") (pinfunction "SHIELD_S1") (pintype "passive"))
      (node (ref "FPCSENSOR9") (pin "S2") (pinfunction "SHIELD_S2") (pintype "passive"))
      (node (ref "LED9") (pin "3") (pinfunction "VSS_3") (pintype "bidirectional"))
    )
    (net (code "172") (name "Net-(LED10-DI)") (class "Default")
      (node (ref "FPCSENSOR10") (pin "4") (pinfunction "4_4") (pintype "passive"))
      (node (ref "LED10") (pin "4") (pinfunction "DI_4") (pintype "bidirectional"))
    )
    (net (code "173") (name "Net-(LED10-VDD)") (class "Default")
      (node (ref "C11") (pin "2") (pinfunction "2_2") (pintype "passive"))
      (node (ref "FPCSENSOR10") (pin "5") (pinfunction "5_5") (pintype "passive"))
      (node (ref "LED10") (pin "1") (pinfunction "VDD_1") (pintype "bidirectional"))
    )
    (net (code "174") (name "Net-(LED10-VSS)") (class "Default")
      (node (ref "C11") (pin "1") (pinfunction "1_1") (pintype "passive"))
      (node (ref "FPCSENSOR10") (pin "1") (pinfunction "1_1") (pintype "passive"))
      (node (ref "FPCSENSOR10") (pin "6") (pinfunction "6_6") (pintype "passive"))
      (node (ref "FPCSENSOR10") (pin "S1") (pinfunction "SHIELD_S1") (pintype "passive"))
      (node (ref "FPCSENSOR10") (pin "S2") (pinfunction "SHIELD_S2") (pintype "passive"))
      (node (ref "LED10") (pin "3") (pinfunction "VSS_3") (pintype "bidirectional"))
    )
    (net (code "175") (name "Net-(LED11-DI)") (class "Default")
      (node (ref "FPCSENSOR11") (pin "4") (pinfunction "4_4") (pintype "passive"))
      (node (ref "LED11") (pin "4") (pinfunction "DI_4") (pintype "bidirectional"))
    )
    (net (code "176") (name "Net-(LED11-VDD)") (class "Default")
      (node (ref "C12") (pin "2") (pinfunction "2_2") (pintype "passive"))
      (node (ref "FPCSENSOR11") (pin "5") (pinfunction "5_5") (pintype "passive"))
      (node (ref "LED11") (pin "1") (pinfunction "VDD_1") (pintype "bidirectional"))
    )
    (net (code "177") (name "Net-(LED11-VSS)") (class "Default")
      (node (ref "C12") (pin "1") (pinfunction "1_1") (pintype "passive"))
      (node (ref "FPCSENSOR11") (pin "1") (pinfunction "1_1") (pintype "passive"))
      (node (ref "FPCSENSOR11") (pin "6") (pinfunction "6_6") (pintype "passive"))
      (node (ref "FPCSENSOR11") (pin "S1") (pinfunction "SHIELD_S1") (pintype "passive"))
      (node (ref "FPCSENSOR11") (pin "S2") (pinfunction "SHIELD_S2") (pintype "passive"))
      (node (ref "LED11") (pin "3") (pinfunction "VSS_3") (pintype "bidirectional"))
    )
    (net (code "178") (name "Net-(S2-O)") (class "Default")
      (node (ref "J3") (pin "VBUS") (pinfunction "VBUS_VBUS") (pintype "power_in"))
      (node (ref "S2") (pin "1") (pinfunction "O_1") (pintype "passive"))
    )
    (net (code "179") (name "Net-(U1-BCK)") (class "Default")
      (node (ref "R9") (pin "2") (pinfunction "2_2") (pintype "passive"))
      (node (ref "U1") (pin "13") (pinfunction "BCK_13") (pintype "input"))
    )
    (net (code "180") (name "Net-(U1-CAPM)") (class "Default")
      (node (ref "C22") (pin "1") (pinfunction "1_1") (pintype "passive"))
      (node (ref "U1") (pin "4") (pinfunction "CAPM_4") (pintype "passive"))
    )
    (net (code "181") (name "Net-(U1-CAPP)") (class "Default")
      (node (ref "C22") (pin "2") (pinfunction "2_2") (pintype "passive"))
      (node (ref "U1") (pin "2") (pinfunction "CAPP_2") (pintype "passive"))
    )
    (net (code "182") (name "Net-(U1-DEMP)") (class "Default")
      (node (ref "DEMP") (pin "2") (pinfunction "2_2") (pintype "passive"))
      (node (ref "U1") (pin "10") (pinfunction "DEMP_10") (pintype "input"))
    )
    (net (code "183") (name "Net-(U1-DIN)") (class "Default")
      (node (ref "R10") (pin "2") (pinfunction "2_2") (pintype "passive"))
      (node (ref "U1") (pin "14") (pinfunction "DIN_14") (pintype "input"))
    )
    (net (code "184") (name "Net-(U1-FLT)") (class "Default")
      (node (ref "LATENCY") (pin "2") (pinfunction "2_2") (pintype "passive"))
      (node (ref "U1") (pin "11") (pinfunction "FLT_11") (pintype "input"))
    )
    (net (code "185") (name "Net-(U1-LDOO)") (class "Default")
      (node (ref "C19") (pin "2") (pinfunction "2_2") (pintype "passive"))
      (node (ref "U1") (pin "18") (pinfunction "LDOO_18") (pintype "power_in"))
    )
    (net (code "186") (name "Net-(U1-LRCK)") (class "Default")
      (node (ref "R11") (pin "2") (pinfunction "2_2") (pintype "passive"))
      (node (ref "U1") (pin "15") (pinfunction "LRCK_15") (pintype "input"))
    )
    (net (code "187") (name "Net-(U1-OUTL)") (class "Default")
      (node (ref "R7") (pin "1") (pinfunction "1_1") (pintype "passive"))
      (node (ref "U1") (pin "6") (pinfunction "OUTL_6") (pintype "output"))
    )
    (net (code "188") (name "Net-(U1-OUTR)") (class "Default")
      (node (ref "R8") (pin "1") (pinfunction "1_1") (pintype "passive"))
      (node (ref "U1") (pin "7") (pinfunction "OUTR_7") (pintype "output"))
    )
    (net (code "189") (name "Net-(U1-VNEG)") (class "Default")
      (node (ref "C21") (pin "1") (pinfunction "1_1") (pintype "passive"))
      (node (ref "U1") (pin "5") (pinfunction "VNEG_5") (pintype "output"))
    )
    (net (code "190") (name "Net-(U2-IN_P)") (class "Default")
      (node (ref "R13") (pin "2") (pinfunction "2_2") (pintype "passive"))
      (node (ref "U2") (pin "3") (pinfunction "IN_P_3") (pintype "input"))
    )
    (net (code "191") (name "Net-(U3-IN_P)") (class "Default")
      (node (ref "R12") (pin "2") (pinfunction "2_2") (pintype "passive"))
      (node (ref "U3") (pin "3") (pinfunction "IN_P_3") (pintype "input"))
    )
    (net (code "192") (name "VCC") (class "Default")
      (node (ref "C27") (pin "1") (pinfunction "1_1") (pintype "passive"))
      (node (ref "C30") (pin "1") (pinfunction "1_1") (pintype "passive"))
      (node (ref "R14") (pin "1") (pinfunction "1_1") (pintype "passive"))
      (node (ref "R15") (pin "1") (pinfunction "1_1") (pintype "passive"))
      (node (ref "U2") (pin "6") (pinfunction "VDD_6") (pintype "power_in"))
      (node (ref "U3") (pin "6") (pinfunction "VDD_6") (pintype "power_in"))
    )
    (net (code "193") (name "unconnected-(H1-MOUNT-PadB3,6)") (class "Default")
      (node (ref "H1") (pin "B3,6") (pinfunction "MOUNT_B3,6") (pintype "passive"))
    )
    (net (code "194") (name "unconnected-(H3-MOUNT-PadB3,6)") (class "Default")
      (node (ref "H3") (pin "B3,6") (pinfunction "MOUNT_B3,6") (pintype "passive"))
    )
    (net (code "195") (name "unconnected-(H4-MOUNT-PadB3,6)") (class "Default")
      (node (ref "H4") (pin "B3,6") (pinfunction "MOUNT_B3,6") (pintype "passive"))
    )
    (net (code "196") (name "unconnected-(H5-MOUNT-PadB3,6)") (class "Default")
      (node (ref "H5") (pin "B3,6") (pinfunction "MOUNT_B3,6") (pintype "passive"))
    )
    (net (code "197") (name "unconnected-(J3-PadD+)") (class "Default")
      (node (ref "J3") (pin "D+") (pinfunction "D+_D+") (pintype "bidirectional"))
    )
    (net (code "198") (name "unconnected-(J3-PadD-)") (class "Default")
      (node (ref "J3") (pin "D-") (pinfunction "D-_D-") (pintype "bidirectional"))
    )
    (net (code "199") (name "unconnected-(J4-Pad5)") (class "Default")
      (node (ref "J4") (pin "5") (pinfunction "5_5") (pintype "bidirectional"))
    )
    (net (code "200") (name "unconnected-(LED0-DO-Pad2)") (class "Default")
      (node (ref "LED0") (pin "2") (pinfunction "DO_2") (pintype "bidirectional"))
    )
    (net (code "201") (name "unconnected-(LED1-DO-Pad2)") (class "Default")
      (node (ref "LED1") (pin "2") (pinfunction "DO_2") (pintype "bidirectional"))
    )
    (net (code "202") (name "unconnected-(LED2-DO-Pad2)") (class "Default")
      (node (ref "LED2") (pin "2") (pinfunction "DO_2") (pintype "bidirectional"))
    )
    (net (code "203") (name "unconnected-(LED3-DO-Pad2)") (class "Default")
      (node (ref "LED3") (pin "2") (pinfunction "DO_2") (pintype "bidirectional"))
    )
    (net (code "204") (name "unconnected-(LED4-DO-Pad2)") (class "Default")
      (node (ref "LED4") (pin "2") (pinfunction "DO_2") (pintype "bidirectional"))
    )
    (net (code "205") (name "unconnected-(LED5-DO-Pad2)") (class "Default")
      (node (ref "LED5") (pin "2") (pinfunction "DO_2") (pintype "bidirectional"))
    )
    (net (code "206") (name "unconnected-(LED6-DO-Pad2)") (class "Default")
      (node (ref "LED6") (pin "2") (pinfunction "DO_2") (pintype "bidirectional"))
    )
    (net (code "207") (name "unconnected-(LED7-DO-Pad2)") (class "Default")
      (node (ref "LED7") (pin "2") (pinfunction "DO_2") (pintype "bidirectional"))
    )
    (net (code "208") (name "unconnected-(LED8-DO-Pad2)") (class "Default")
      (node (ref "LED8") (pin "2") (pinfunction "DO_2") (pintype "bidirectional"))
    )
    (net (code "209") (name "unconnected-(LED9-DO-Pad2)") (class "Default")
      (node (ref "LED9") (pin "2") (pinfunction "DO_2") (pintype "bidirectional"))
    )
    (net (code "210") (name "unconnected-(LED10-DO-Pad2)") (class "Default")
      (node (ref "LED10") (pin "2") (pinfunction "DO_2") (pintype "bidirectional"))
    )
    (net (code "211") (name "unconnected-(LED11-DO-Pad2)") (class "Default")
      (node (ref "LED11") (pin "2") (pinfunction "DO_2") (pintype "bidirectional"))
    )
    (net (code "212") (name "unconnected-(S2-S-Pad3)") (class "Default")
      (node (ref "S2") (pin "3") (pinfunction "S_3") (pintype "passive"))
    )
    (net (code "213") (name "unconnected-(U$1-PadPGM)") (class "Default")
      (node (ref "U$1") (pin "PGM") (pinfunction "PGM_PGM") (pintype "bidirectional"))
    )
    (net (code "214") (name "unconnected-(U1-XSMT-Pad17)") (class "Default")
      (node (ref "U1") (pin "17") (pinfunction "XSMT_17") (pintype "input"))
    )
    (net (code "215") (name "unconnected-(U2-NC-Pad2)") (class "Default")
      (node (ref "U2") (pin "2") (pinfunction "NC_2") (pintype "no_connect"))
    )
    (net (code "216") (name "unconnected-(U3-NC-Pad2)") (class "Default")
      (node (ref "U3") (pin "2") (pinfunction "NC_2") (pintype "no_connect"))
    )
  )
)
